# Logitech_Gamepad.net
KiCad netlist of a schematic drawn in EAGLE
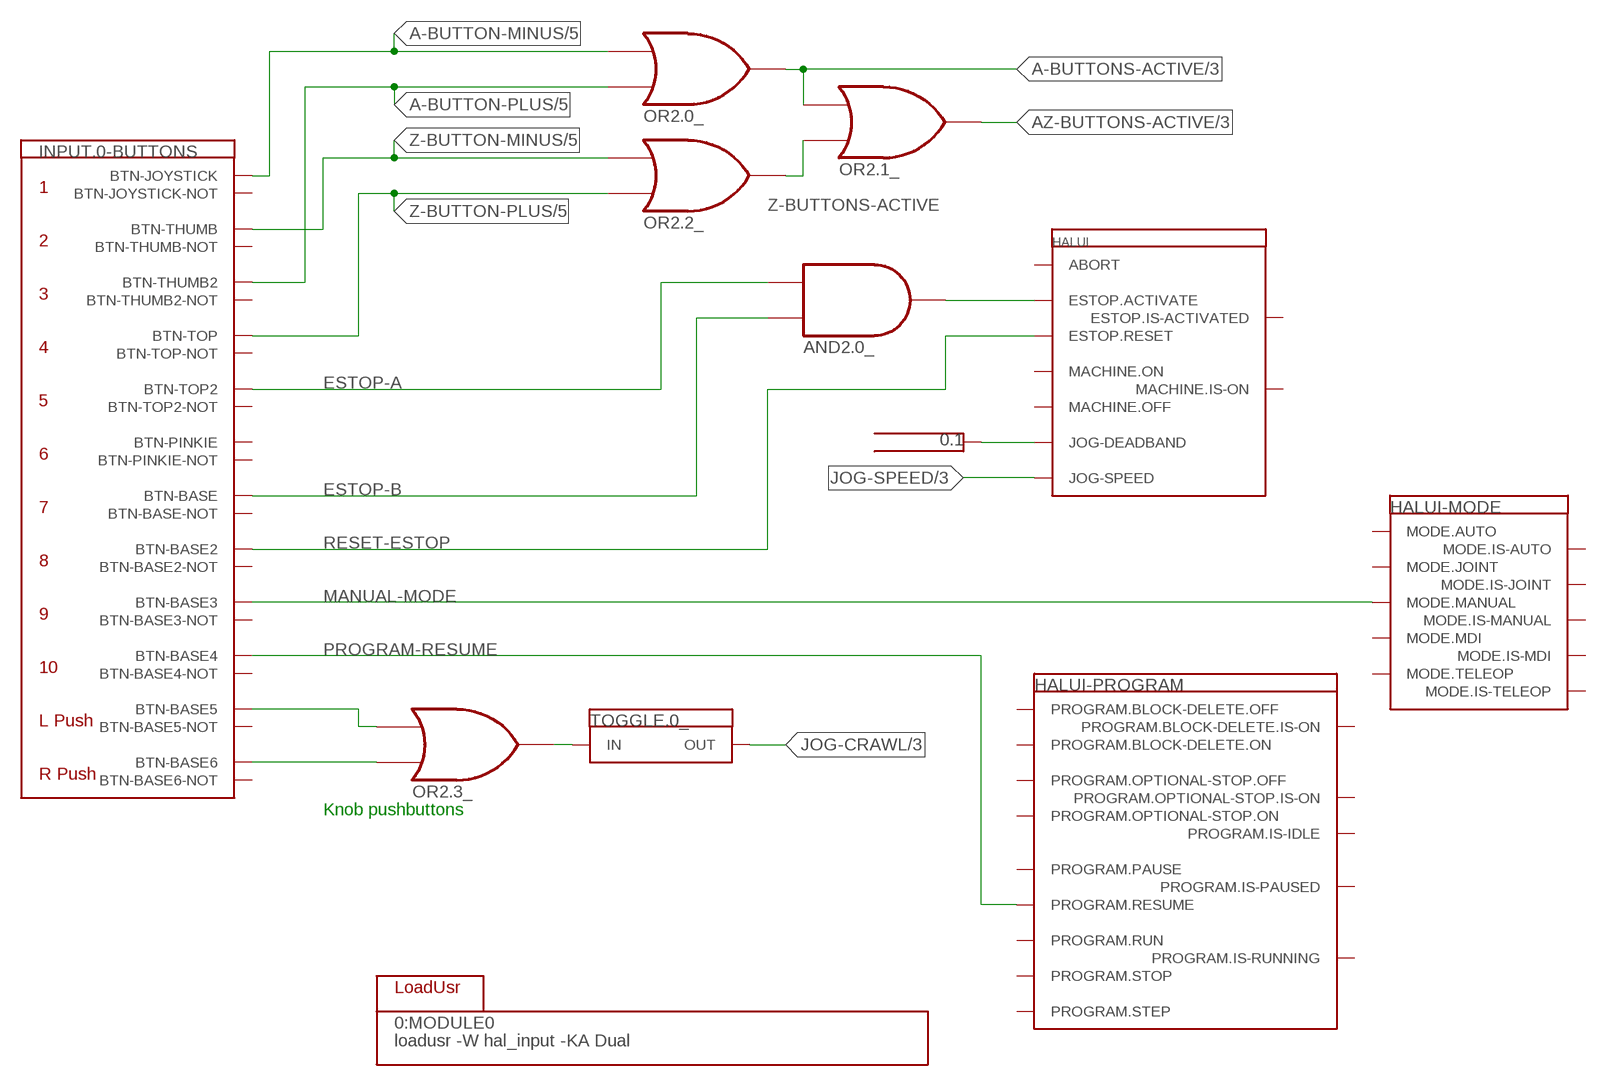
[diagram p0: schematic, sheet 1]
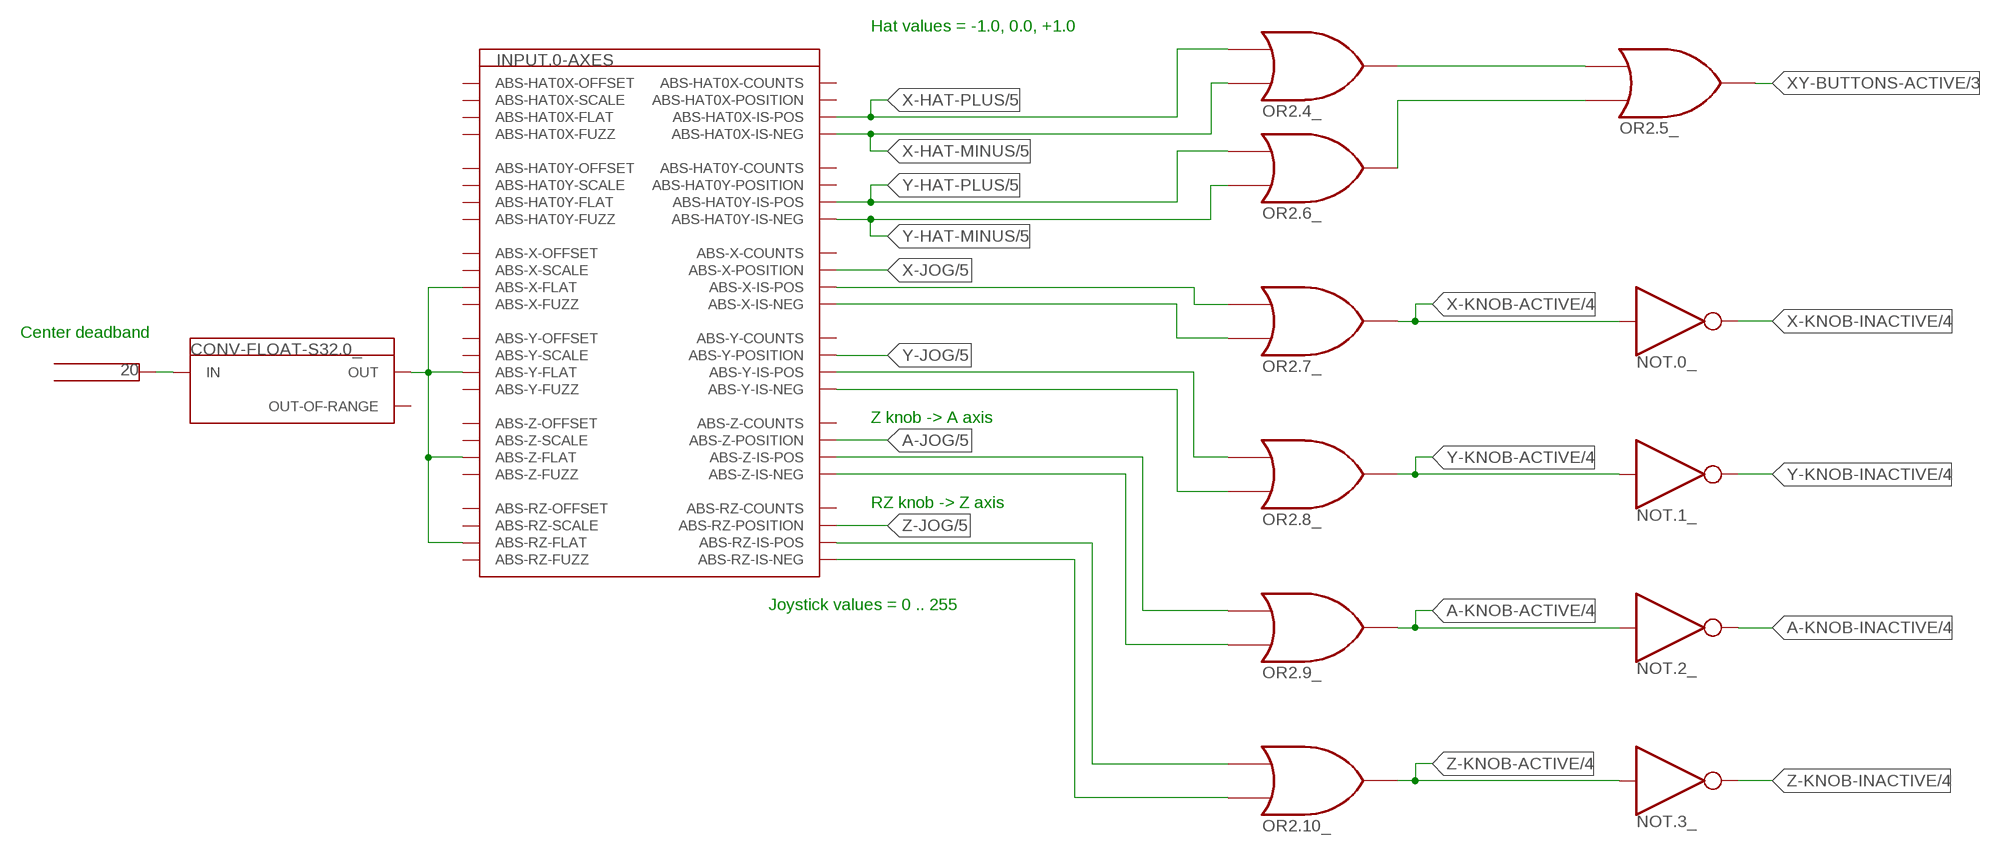
[diagram p1: schematic, sheet 2]
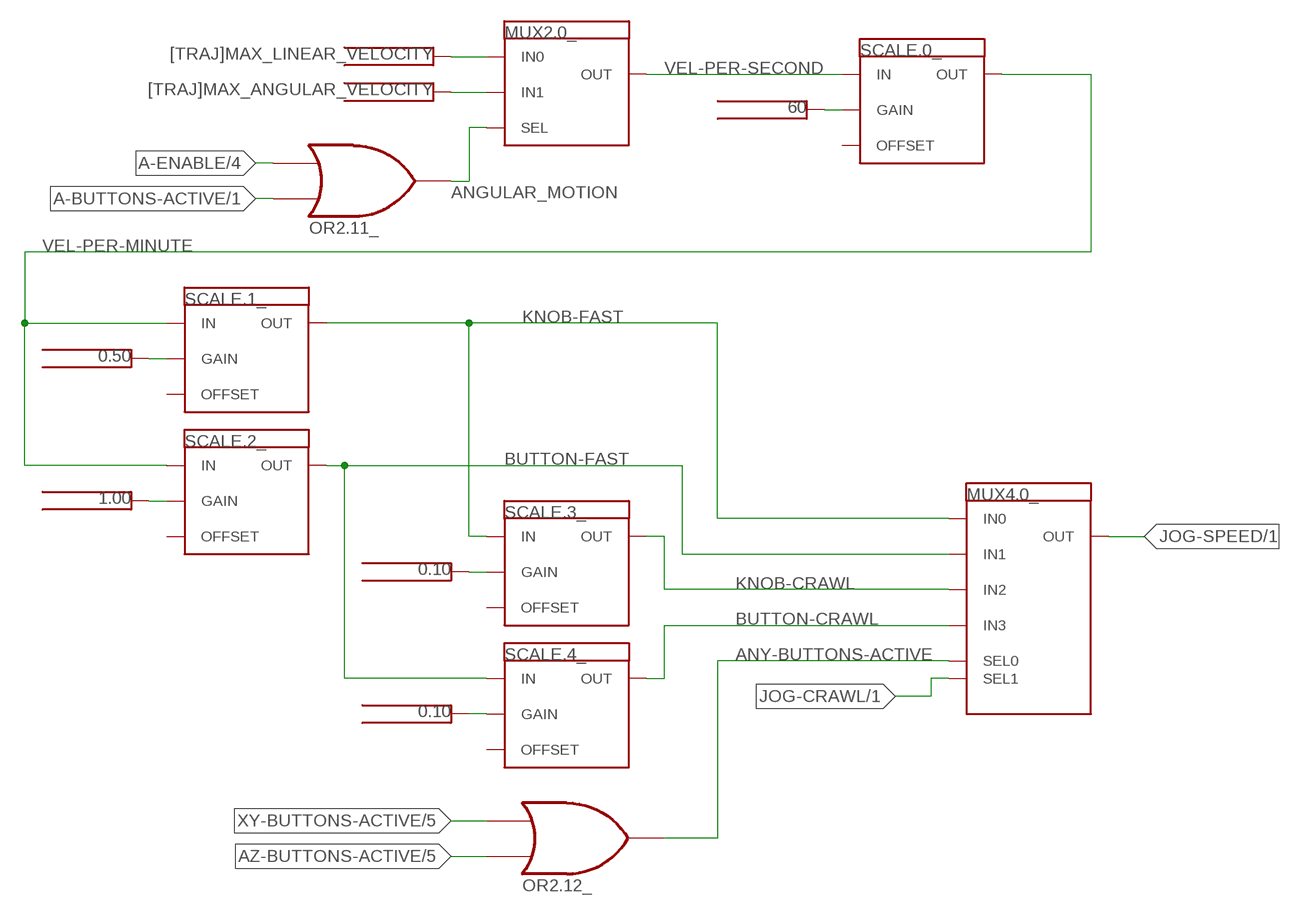
[diagram p2: schematic, sheet 3]
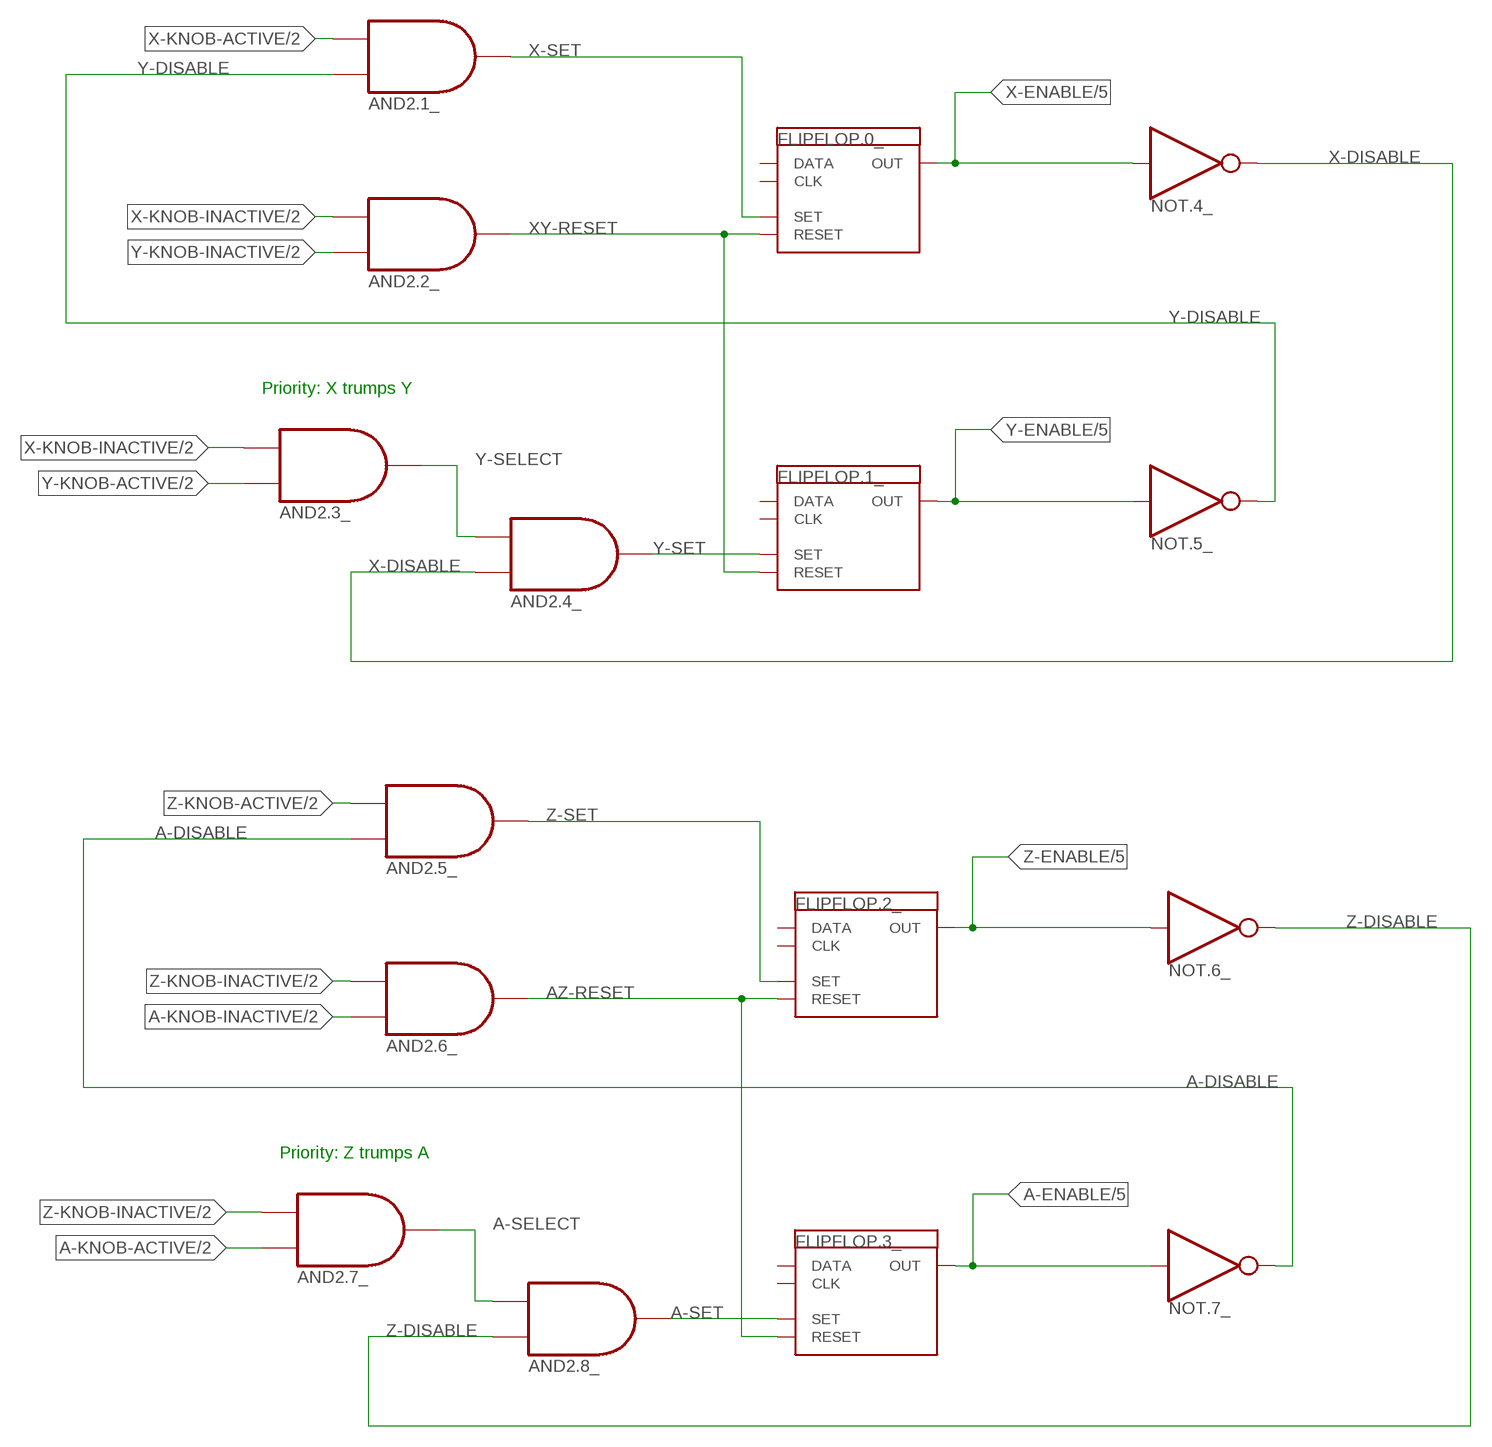
[diagram p3: schematic, sheet 4]
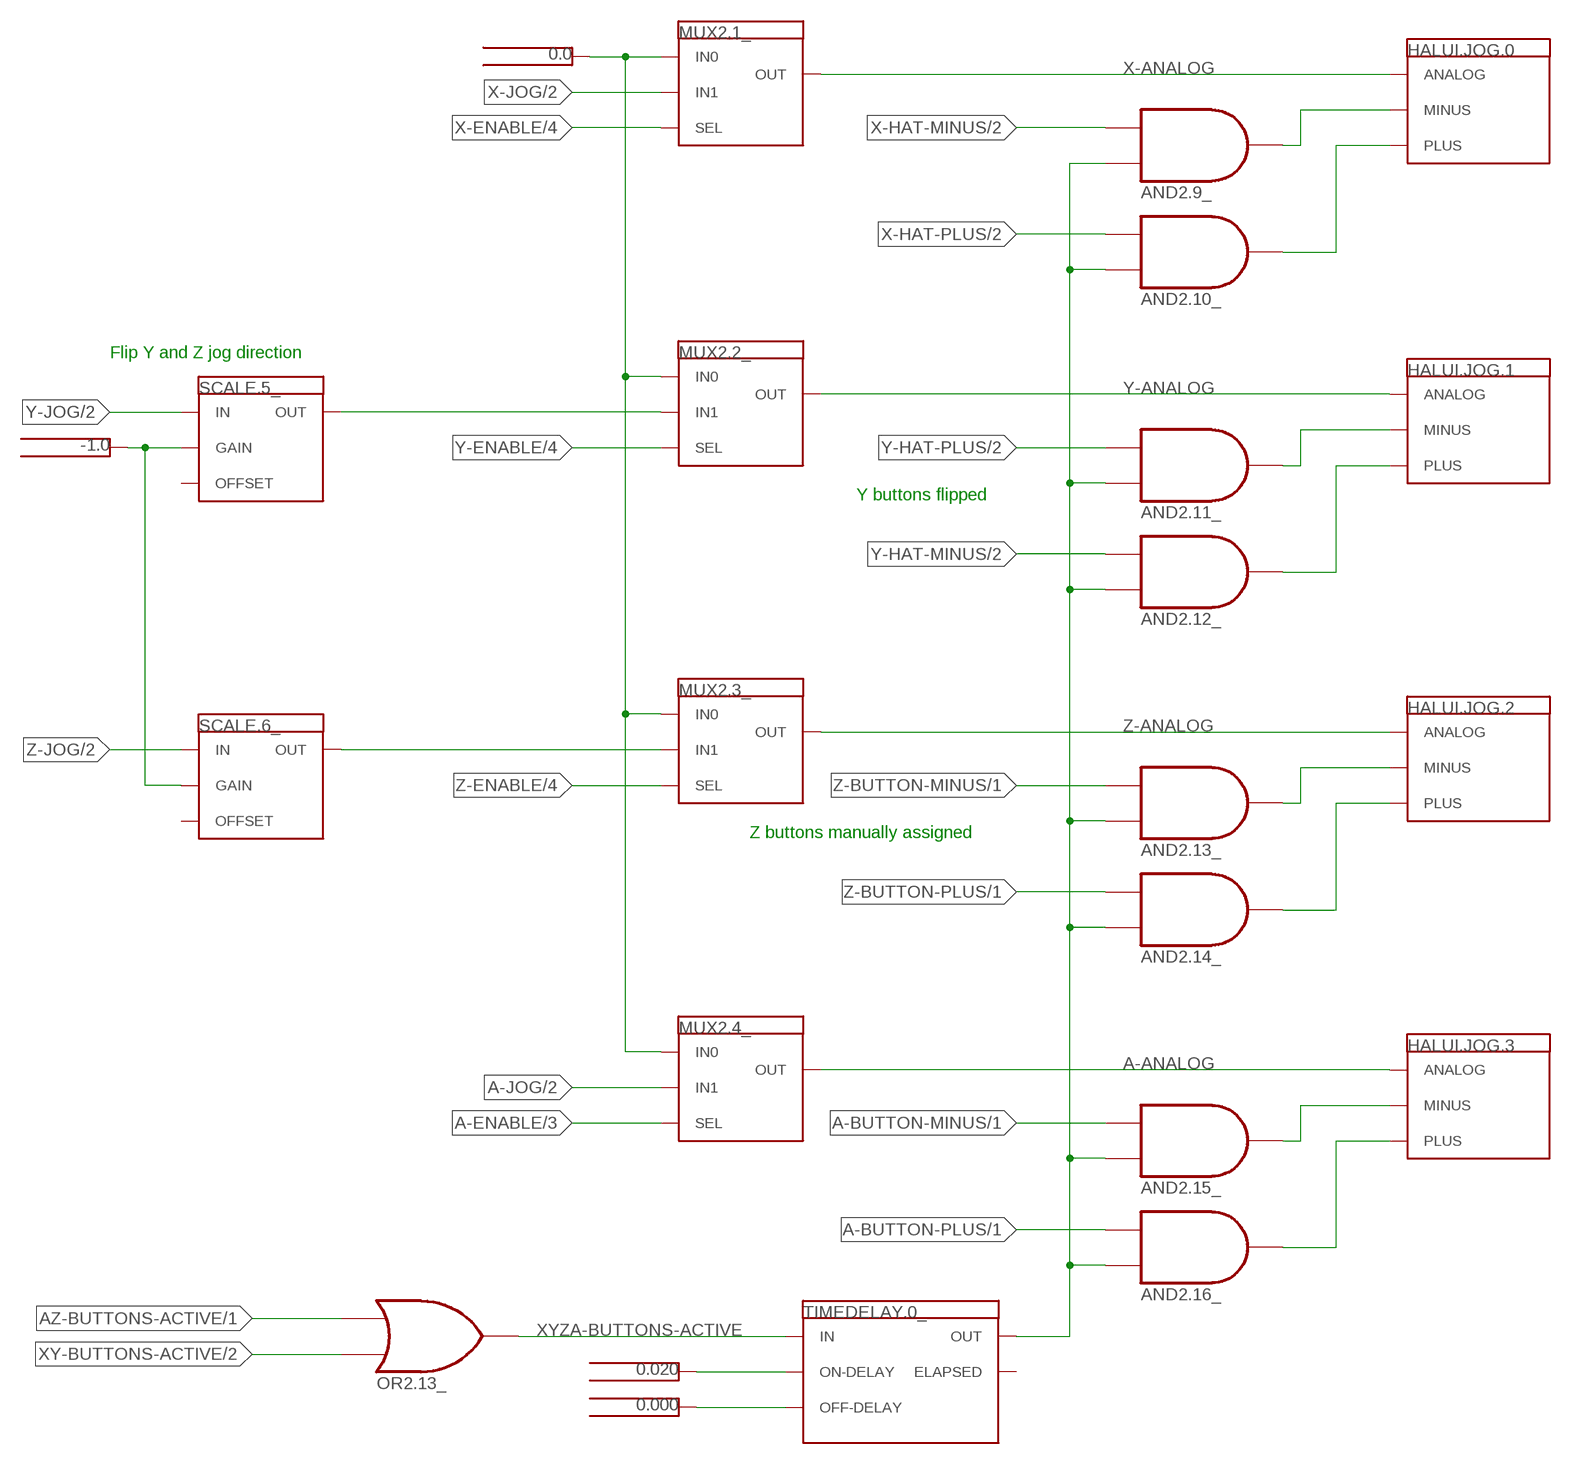
[diagram p4: schematic, sheet 5]
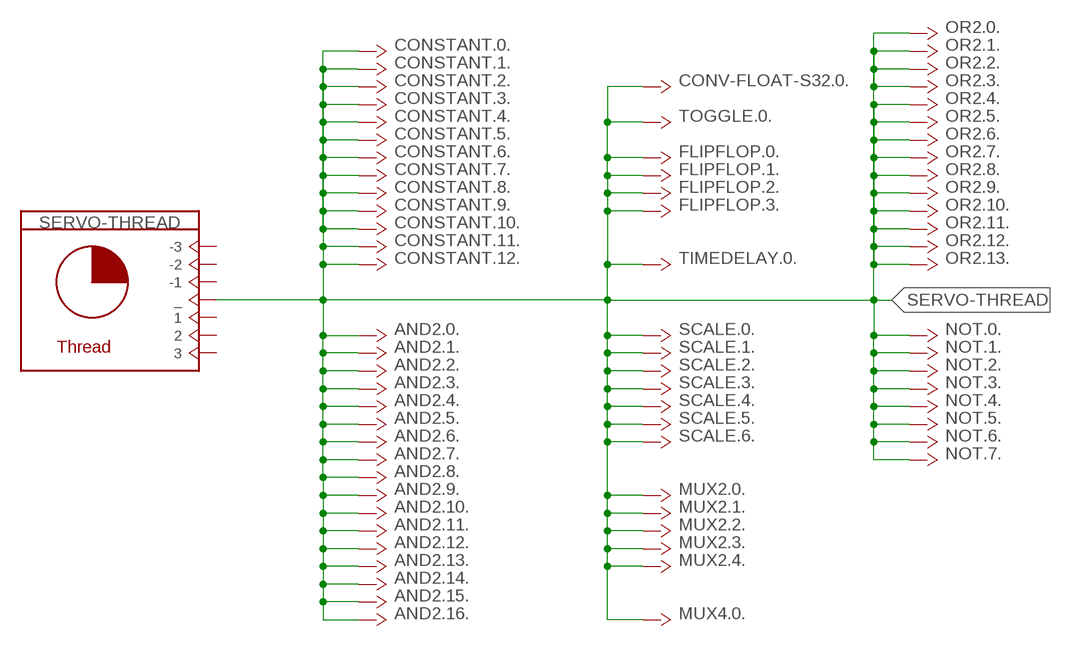
[diagram p5: schematic, sheet 6]

(export (version "E")
  (design (tool "Eeschema 10.0.6"))
  (components
    (comp (ref "AND2.9")
      (value "AND2")
      (footprint "eagle-import:DUMMY")
      (libsource (lib "eagle-import") (part "AND2"))
    )
    (comp (ref "AND2.10")
      (value "AND2")
      (footprint "eagle-import:DUMMY")
      (libsource (lib "eagle-import") (part "AND2"))
    )
    (comp (ref "AND2.11")
      (value "AND2")
      (footprint "eagle-import:DUMMY")
      (libsource (lib "eagle-import") (part "AND2"))
    )
    (comp (ref "AND2.12")
      (value "AND2")
      (footprint "eagle-import:DUMMY")
      (libsource (lib "eagle-import") (part "AND2"))
    )
    (comp (ref "AND2.13")
      (value "AND2")
      (footprint "eagle-import:DUMMY")
      (libsource (lib "eagle-import") (part "AND2"))
    )
    (comp (ref "AND2.14")
      (value "AND2")
      (footprint "eagle-import:DUMMY")
      (libsource (lib "eagle-import") (part "AND2"))
    )
    (comp (ref "AND2.15")
      (value "AND2")
      (footprint "eagle-import:DUMMY")
      (libsource (lib "eagle-import") (part "AND2"))
    )
    (comp (ref "AND2.16")
      (value "AND2")
      (footprint "eagle-import:DUMMY")
      (libsource (lib "eagle-import") (part "AND2"))
    )
    (comp (ref "CONSTANT.9")
      (value "0.0")
      (footprint "eagle-import:DUMMY")
      (libsource (lib "eagle-import") (part "CONSTANT"))
    )
    (comp (ref "CONSTANT.10")
      (value "-1.0")
      (footprint "eagle-import:DUMMY")
      (libsource (lib "eagle-import") (part "CONSTANT"))
    )
    (comp (ref "CONSTANT.11")
      (value "0.020")
      (footprint "eagle-import:DUMMY")
      (libsource (lib "eagle-import") (part "CONSTANT"))
    )
    (comp (ref "CONSTANT.12")
      (value "0.000")
      (footprint "eagle-import:DUMMY")
      (libsource (lib "eagle-import") (part "CONSTANT"))
    )
    (comp (ref "HALUI.JOG.0")
      (value "HALUI.JOG")
      (footprint "eagle-import:DUMMY")
      (libsource (lib "eagle-import") (part "HALUI.JOG"))
    )
    (comp (ref "HALUI.JOG.1")
      (value "HALUI.JOG")
      (footprint "eagle-import:DUMMY")
      (libsource (lib "eagle-import") (part "HALUI.JOG"))
    )
    (comp (ref "HALUI.JOG.2")
      (value "HALUI.JOG")
      (footprint "eagle-import:DUMMY")
      (libsource (lib "eagle-import") (part "HALUI.JOG"))
    )
    (comp (ref "HALUI.JOG.3")
      (value "HALUI.JOG")
      (footprint "eagle-import:DUMMY")
      (libsource (lib "eagle-import") (part "HALUI.JOG"))
    )
    (comp (ref "MUX2.1")
      (value "MUX2")
      (footprint "eagle-import:DUMMY")
      (libsource (lib "eagle-import") (part "MUX2"))
    )
    (comp (ref "MUX2.2")
      (value "MUX2")
      (footprint "eagle-import:DUMMY")
      (libsource (lib "eagle-import") (part "MUX2"))
    )
    (comp (ref "MUX2.3")
      (value "MUX2")
      (footprint "eagle-import:DUMMY")
      (libsource (lib "eagle-import") (part "MUX2"))
    )
    (comp (ref "MUX2.4")
      (value "MUX2")
      (footprint "eagle-import:DUMMY")
      (libsource (lib "eagle-import") (part "MUX2"))
    )
    (comp (ref "OR2.13")
      (value "OR2")
      (footprint "eagle-import:DUMMY")
      (libsource (lib "eagle-import") (part "OR2"))
    )
    (comp (ref "SCALE.5")
      (value "SCALE")
      (footprint "eagle-import:DUMMY")
      (libsource (lib "eagle-import") (part "SCALE"))
    )
    (comp (ref "SCALE.6")
      (value "SCALE")
      (footprint "eagle-import:DUMMY")
      (libsource (lib "eagle-import") (part "SCALE"))
    )
    (comp (ref "TIMEDELAY.0")
      (value "TIMEDELAY")
      (footprint "eagle-import:DUMMY")
      (libsource (lib "eagle-import") (part "TIMEDELAY"))
    )
    (comp (ref "CONSTANT.1")
      (value "20")
      (footprint "eagle-import:DUMMY")
      (libsource (lib "eagle-import") (part "CONSTANT"))
    )
    (comp (ref "CONV-FLOAT-S32.0")
      (value "CONV_FLOAT_S32")
      (footprint "eagle-import:DUMMY")
      (libsource (lib "eagle-import") (part "CONV_FLOAT_S32"))
    )
    (comp (ref "INPUT.0")
      (value "LOGITECH-DUAL-ACTION-GAMEPAD")
      (footprint "eagle-import:DUMMY")
      (libsource (lib "eagle-import") (part "LOGITECH-DUAL-ACTION-GAMEPAD"))
    )
    (comp (ref "NOT.0")
      (value "NOT")
      (footprint "eagle-import:DUMMY")
      (libsource (lib "eagle-import") (part "NOT"))
    )
    (comp (ref "NOT.1")
      (value "NOT")
      (footprint "eagle-import:DUMMY")
      (libsource (lib "eagle-import") (part "NOT"))
    )
    (comp (ref "NOT.2")
      (value "NOT")
      (footprint "eagle-import:DUMMY")
      (libsource (lib "eagle-import") (part "NOT"))
    )
    (comp (ref "NOT.3")
      (value "NOT")
      (footprint "eagle-import:DUMMY")
      (libsource (lib "eagle-import") (part "NOT"))
    )
    (comp (ref "OR2.4")
      (value "OR2")
      (footprint "eagle-import:DUMMY")
      (libsource (lib "eagle-import") (part "OR2"))
    )
    (comp (ref "OR2.5")
      (value "OR2")
      (footprint "eagle-import:DUMMY")
      (libsource (lib "eagle-import") (part "OR2"))
    )
    (comp (ref "OR2.6")
      (value "OR2")
      (footprint "eagle-import:DUMMY")
      (libsource (lib "eagle-import") (part "OR2"))
    )
    (comp (ref "OR2.7")
      (value "OR2")
      (footprint "eagle-import:DUMMY")
      (libsource (lib "eagle-import") (part "OR2"))
    )
    (comp (ref "OR2.8")
      (value "OR2")
      (footprint "eagle-import:DUMMY")
      (libsource (lib "eagle-import") (part "OR2"))
    )
    (comp (ref "OR2.9")
      (value "OR2")
      (footprint "eagle-import:DUMMY")
      (libsource (lib "eagle-import") (part "OR2"))
    )
    (comp (ref "OR2.10")
      (value "OR2")
      (footprint "eagle-import:DUMMY")
      (libsource (lib "eagle-import") (part "OR2"))
    )
    (comp (ref "CONSTANT.2")
      (value "[TRAJ]MAX_LINEAR_VELOCITY")
      (footprint "eagle-import:DUMMY")
      (libsource (lib "eagle-import") (part "CONSTANT"))
    )
    (comp (ref "CONSTANT.3")
      (value "[TRAJ]MAX_ANGULAR_VELOCITY")
      (footprint "eagle-import:DUMMY")
      (libsource (lib "eagle-import") (part "CONSTANT"))
    )
    (comp (ref "CONSTANT.4")
      (value "60")
      (footprint "eagle-import:DUMMY")
      (libsource (lib "eagle-import") (part "CONSTANT"))
    )
    (comp (ref "CONSTANT.5")
      (value "0.50")
      (footprint "eagle-import:DUMMY")
      (libsource (lib "eagle-import") (part "CONSTANT"))
    )
    (comp (ref "CONSTANT.6")
      (value "1.00")
      (footprint "eagle-import:DUMMY")
      (libsource (lib "eagle-import") (part "CONSTANT"))
    )
    (comp (ref "CONSTANT.7")
      (value "0.10")
      (footprint "eagle-import:DUMMY")
      (libsource (lib "eagle-import") (part "CONSTANT"))
    )
    (comp (ref "CONSTANT.8")
      (value "0.10")
      (footprint "eagle-import:DUMMY")
      (libsource (lib "eagle-import") (part "CONSTANT"))
    )
    (comp (ref "MUX2.0")
      (value "MUX2")
      (footprint "eagle-import:DUMMY")
      (libsource (lib "eagle-import") (part "MUX2"))
    )
    (comp (ref "MUX4.0")
      (value "MUX4")
      (footprint "eagle-import:DUMMY")
      (libsource (lib "eagle-import") (part "MUX4"))
    )
    (comp (ref "OR2.11")
      (value "OR2")
      (footprint "eagle-import:DUMMY")
      (libsource (lib "eagle-import") (part "OR2"))
    )
    (comp (ref "OR2.12")
      (value "OR2")
      (footprint "eagle-import:DUMMY")
      (libsource (lib "eagle-import") (part "OR2"))
    )
    (comp (ref "SCALE.0")
      (value "SCALE")
      (footprint "eagle-import:DUMMY")
      (libsource (lib "eagle-import") (part "SCALE"))
    )
    (comp (ref "SCALE.1")
      (value "SCALE")
      (footprint "eagle-import:DUMMY")
      (libsource (lib "eagle-import") (part "SCALE"))
    )
    (comp (ref "SCALE.2")
      (value "SCALE")
      (footprint "eagle-import:DUMMY")
      (libsource (lib "eagle-import") (part "SCALE"))
    )
    (comp (ref "SCALE.3")
      (value "SCALE")
      (footprint "eagle-import:DUMMY")
      (libsource (lib "eagle-import") (part "SCALE"))
    )
    (comp (ref "SCALE.4")
      (value "SCALE")
      (footprint "eagle-import:DUMMY")
      (libsource (lib "eagle-import") (part "SCALE"))
    )
    (comp (ref "AND2.1")
      (value "AND2")
      (footprint "eagle-import:DUMMY")
      (libsource (lib "eagle-import") (part "AND2"))
    )
    (comp (ref "AND2.2")
      (value "AND2")
      (footprint "eagle-import:DUMMY")
      (libsource (lib "eagle-import") (part "AND2"))
    )
    (comp (ref "AND2.3")
      (value "AND2")
      (footprint "eagle-import:DUMMY")
      (libsource (lib "eagle-import") (part "AND2"))
    )
    (comp (ref "AND2.4")
      (value "AND2")
      (footprint "eagle-import:DUMMY")
      (libsource (lib "eagle-import") (part "AND2"))
    )
    (comp (ref "AND2.5")
      (value "AND2")
      (footprint "eagle-import:DUMMY")
      (libsource (lib "eagle-import") (part "AND2"))
    )
    (comp (ref "AND2.6")
      (value "AND2")
      (footprint "eagle-import:DUMMY")
      (libsource (lib "eagle-import") (part "AND2"))
    )
    (comp (ref "AND2.7")
      (value "AND2")
      (footprint "eagle-import:DUMMY")
      (libsource (lib "eagle-import") (part "AND2"))
    )
    (comp (ref "AND2.8")
      (value "AND2")
      (footprint "eagle-import:DUMMY")
      (libsource (lib "eagle-import") (part "AND2"))
    )
    (comp (ref "FLIPFLOP.0")
      (value "FLIPFLOP")
      (footprint "eagle-import:DUMMY")
      (libsource (lib "eagle-import") (part "FLIPFLOP"))
    )
    (comp (ref "FLIPFLOP.1")
      (value "FLIPFLOP")
      (footprint "eagle-import:DUMMY")
      (libsource (lib "eagle-import") (part "FLIPFLOP"))
    )
    (comp (ref "FLIPFLOP.2")
      (value "FLIPFLOP")
      (footprint "eagle-import:DUMMY")
      (libsource (lib "eagle-import") (part "FLIPFLOP"))
    )
    (comp (ref "FLIPFLOP.3")
      (value "FLIPFLOP")
      (footprint "eagle-import:DUMMY")
      (libsource (lib "eagle-import") (part "FLIPFLOP"))
    )
    (comp (ref "NOT.4")
      (value "NOT")
      (footprint "eagle-import:DUMMY")
      (libsource (lib "eagle-import") (part "NOT"))
    )
    (comp (ref "NOT.5")
      (value "NOT")
      (footprint "eagle-import:DUMMY")
      (libsource (lib "eagle-import") (part "NOT"))
    )
    (comp (ref "NOT.6")
      (value "NOT")
      (footprint "eagle-import:DUMMY")
      (libsource (lib "eagle-import") (part "NOT"))
    )
    (comp (ref "NOT.7")
      (value "NOT")
      (footprint "eagle-import:DUMMY")
      (libsource (lib "eagle-import") (part "NOT"))
    )
    (comp (ref "AND2.0")
      (value "AND2")
      (footprint "eagle-import:DUMMY")
      (libsource (lib "eagle-import") (part "AND2"))
    )
    (comp (ref "CONSTANT.0")
      (value "0.1")
      (footprint "eagle-import:DUMMY")
      (libsource (lib "eagle-import") (part "CONSTANT"))
    )
    (comp (ref "OR2.0")
      (value "OR2")
      (footprint "eagle-import:DUMMY")
      (libsource (lib "eagle-import") (part "OR2"))
    )
    (comp (ref "OR2.1")
      (value "OR2")
      (footprint "eagle-import:DUMMY")
      (libsource (lib "eagle-import") (part "OR2"))
    )
    (comp (ref "OR2.2")
      (value "OR2")
      (footprint "eagle-import:DUMMY")
      (libsource (lib "eagle-import") (part "OR2"))
    )
    (comp (ref "OR2.3")
      (value "OR2")
      (footprint "eagle-import:DUMMY")
      (libsource (lib "eagle-import") (part "OR2"))
    )
    (comp (ref "SERVO-THREAD")
      (value "THREAD")
      (footprint "eagle-import:DUMMY")
      (libsource (lib "eagle-import") (part "THREAD"))
    )
    (comp (ref "TOGGLE.0")
      (value "TOGGLE")
      (footprint "eagle-import:DUMMY")
      (libsource (lib "eagle-import") (part "TOGGLE"))
    )
    (comp (ref "HALUI")
      (value "HALUI")
      (footprint "eagle-import:DUMMY")
      (libsource (lib "eagle-import") (part "HALUI"))
    )
  )
  (nets
    (net (code "1") (name "A-ANALOG") (class "Default")
      (node (ref "HALUI.JOG.3") (pin "P$1") (pinfunction "ANALOG_P$1") (pintype "input"))
      (node (ref "MUX2.4") (pin "P$4") (pinfunction "OUT_P$4") (pintype "output"))
    )
    (net (code "2") (name "A-BUTTON-MINUS") (class "Default")
      (node (ref "AND2.15") (pin "P$1") (pinfunction "IN0_P$1") (pintype "input"))
      (node (ref "INPUT.0") (pin "P$61") (pinfunction "BTN-JOYSTICK_P$61") (pintype "output"))
      (node (ref "OR2.0") (pin "P$2") (pinfunction "IN0_P$2") (pintype "input"))
    )
    (net (code "3") (name "A-BUTTON-PLUS") (class "Default")
      (node (ref "AND2.16") (pin "P$1") (pinfunction "IN0_P$1") (pintype "input"))
      (node (ref "INPUT.0") (pin "P$67") (pinfunction "BTN-THUMB2_P$67") (pintype "output"))
      (node (ref "OR2.0") (pin "P$3") (pinfunction "IN1_P$3") (pintype "input"))
    )
    (net (code "4") (name "A-BUTTONS-ACTIVE") (class "Default")
      (node (ref "OR2.0") (pin "P$4") (pinfunction "OUT_P$4") (pintype "output"))
      (node (ref "OR2.1") (pin "P$2") (pinfunction "IN0_P$2") (pintype "input"))
      (node (ref "OR2.11") (pin "P$3") (pinfunction "IN1_P$3") (pintype "input"))
    )
    (net (code "5") (name "A-DISABLE") (class "Default")
      (node (ref "AND2.5") (pin "P$2") (pinfunction "IN1_P$2") (pintype "input"))
      (node (ref "NOT.7") (pin "P$2") (pinfunction "OUT_P$2") (pintype "output"))
    )
    (net (code "6") (name "A-ENABLE") (class "Default")
      (node (ref "FLIPFLOP.3") (pin "P$3") (pinfunction "OUT_P$3") (pintype "output"))
      (node (ref "MUX2.4") (pin "P$5") (pinfunction "SEL_P$5") (pintype "input"))
      (node (ref "NOT.7") (pin "P$1") (pinfunction "IN_P$1") (pintype "input"))
      (node (ref "OR2.11") (pin "P$2") (pinfunction "IN0_P$2") (pintype "input"))
    )
    (net (code "7") (name "A-JOG") (class "Default")
      (node (ref "INPUT.0") (pin "P$47") (pinfunction "ABS-Z-POSITION_P$47") (pintype "output"))
      (node (ref "MUX2.4") (pin "P$3") (pinfunction "IN1_P$3") (pintype "input"))
    )
    (net (code "8") (name "A-KNOB-ACTIVE") (class "Default")
      (node (ref "AND2.7") (pin "P$2") (pinfunction "IN1_P$2") (pintype "input"))
      (node (ref "NOT.2") (pin "P$1") (pinfunction "IN_P$1") (pintype "input"))
      (node (ref "OR2.9") (pin "P$4") (pinfunction "OUT_P$4") (pintype "output"))
    )
    (net (code "9") (name "A-KNOB-INACTIVE") (class "Default")
      (node (ref "AND2.6") (pin "P$2") (pinfunction "IN1_P$2") (pintype "input"))
      (node (ref "NOT.2") (pin "P$2") (pinfunction "OUT_P$2") (pintype "output"))
    )
    (net (code "10") (name "A-SELECT") (class "Default")
      (node (ref "AND2.7") (pin "P$3") (pinfunction "OUT_P$3") (pintype "output"))
      (node (ref "AND2.8") (pin "P$1") (pinfunction "IN0_P$1") (pintype "input"))
    )
    (net (code "11") (name "A-SET") (class "Default")
      (node (ref "AND2.8") (pin "P$3") (pinfunction "OUT_P$3") (pintype "output"))
      (node (ref "FLIPFLOP.3") (pin "P$5") (pinfunction "SET_P$5") (pintype "input"))
    )
    (net (code "12") (name "ANGULAR_MOTION") (class "Default")
      (node (ref "MUX2.0") (pin "P$5") (pinfunction "SEL_P$5") (pintype "input"))
      (node (ref "OR2.11") (pin "P$4") (pinfunction "OUT_P$4") (pintype "output"))
    )
    (net (code "13") (name "ANY-BUTTONS-ACTIVE") (class "Default")
      (node (ref "MUX4.0") (pin "P$7") (pinfunction "SEL0_P$7") (pintype "input"))
      (node (ref "OR2.12") (pin "P$4") (pinfunction "OUT_P$4") (pintype "output"))
    )
    (net (code "14") (name "AZ-BUTTONS-ACTIVE") (class "Default")
      (node (ref "OR2.1") (pin "P$4") (pinfunction "OUT_P$4") (pintype "output"))
      (node (ref "OR2.12") (pin "P$3") (pinfunction "IN1_P$3") (pintype "input"))
      (node (ref "OR2.13") (pin "P$2") (pinfunction "IN0_P$2") (pintype "input"))
    )
    (net (code "15") (name "AZ-RESET") (class "Default")
      (node (ref "AND2.6") (pin "P$3") (pinfunction "OUT_P$3") (pintype "output"))
      (node (ref "FLIPFLOP.2") (pin "P$4") (pinfunction "RESET_P$4") (pintype "input"))
      (node (ref "FLIPFLOP.3") (pin "P$4") (pinfunction "RESET_P$4") (pintype "input"))
    )
    (net (code "16") (name "BUTTON-CRAWL") (class "Default")
      (node (ref "MUX4.0") (pin "P$5") (pinfunction "IN3_P$5") (pintype "input"))
      (node (ref "SCALE.4") (pin "P$5") (pinfunction "OUT_P$5") (pintype "output"))
    )
    (net (code "17") (name "BUTTON-FAST") (class "Default")
      (node (ref "MUX4.0") (pin "P$3") (pinfunction "IN1_P$3") (pintype "input"))
      (node (ref "SCALE.2") (pin "P$5") (pinfunction "OUT_P$5") (pintype "output"))
      (node (ref "SCALE.4") (pin "P$3") (pinfunction "IN_P$3") (pintype "input"))
    )
    (net (code "18") (name "ESTOP-A") (class "Default")
      (node (ref "AND2.0") (pin "P$1") (pinfunction "IN0_P$1") (pintype "input"))
      (node (ref "INPUT.0") (pin "P$71") (pinfunction "BTN-TOP2_P$71") (pintype "output"))
    )
    (net (code "19") (name "ESTOP-B") (class "Default")
      (node (ref "AND2.0") (pin "P$2") (pinfunction "IN1_P$2") (pintype "input"))
      (node (ref "INPUT.0") (pin "P$49") (pinfunction "BTN-BASE_P$49") (pintype "output"))
    )
    (net (code "20") (name "JOG-CRAWL") (class "Default")
      (node (ref "MUX4.0") (pin "P$8") (pinfunction "SEL1_P$8") (pintype "input"))
      (node (ref "TOGGLE.0") (pin "P$3") (pinfunction "OUT_P$3") (pintype "output"))
    )
    (net (code "21") (name "JOG-SPEED") (class "Default")
      (node (ref "HALUI") (pin "P$82") (pinfunction "JOG-SPEED_P$82") (pintype "input"))
      (node (ref "MUX4.0") (pin "P$6") (pinfunction "OUT_P$6") (pintype "output"))
    )
    (net (code "22") (name "KNOB-CRAWL") (class "Default")
      (node (ref "MUX4.0") (pin "P$4") (pinfunction "IN2_P$4") (pintype "input"))
      (node (ref "SCALE.3") (pin "P$5") (pinfunction "OUT_P$5") (pintype "output"))
    )
    (net (code "23") (name "KNOB-FAST") (class "Default")
      (node (ref "MUX4.0") (pin "P$2") (pinfunction "IN0_P$2") (pintype "input"))
      (node (ref "SCALE.1") (pin "P$5") (pinfunction "OUT_P$5") (pintype "output"))
      (node (ref "SCALE.3") (pin "P$3") (pinfunction "IN_P$3") (pintype "input"))
    )
    (net (code "24") (name "MANUAL-MODE") (class "Default")
      (node (ref "HALUI") (pin "P$72") (pinfunction "MODE.MANUAL_P$72") (pintype "input"))
      (node (ref "INPUT.0") (pin "P$53") (pinfunction "BTN-BASE3_P$53") (pintype "output"))
    )
    (net (code "25") (name "Net-(AND2.0B-OUT)") (class "Default")
      (node (ref "AND2.0") (pin "P$3") (pinfunction "OUT_P$3") (pintype "output"))
      (node (ref "HALUI") (pin "P$2") (pinfunction "ESTOP.ACTIVATE_P$2") (pintype "input"))
    )
    (net (code "26") (name "Net-(AND2.9B-OUT)") (class "Default")
      (node (ref "AND2.9") (pin "P$3") (pinfunction "OUT_P$3") (pintype "output"))
      (node (ref "HALUI.JOG.0") (pin "P$2") (pinfunction "MINUS_P$2") (pintype "input"))
    )
    (net (code "27") (name "Net-(AND2.10B-IN1)") (class "Default")
      (node (ref "AND2.10") (pin "P$2") (pinfunction "IN1_P$2") (pintype "input"))
      (node (ref "AND2.11") (pin "P$2") (pinfunction "IN1_P$2") (pintype "input"))
      (node (ref "AND2.12") (pin "P$2") (pinfunction "IN1_P$2") (pintype "input"))
      (node (ref "AND2.13") (pin "P$2") (pinfunction "IN1_P$2") (pintype "input"))
      (node (ref "AND2.14") (pin "P$2") (pinfunction "IN1_P$2") (pintype "input"))
      (node (ref "AND2.15") (pin "P$2") (pinfunction "IN1_P$2") (pintype "input"))
      (node (ref "AND2.16") (pin "P$2") (pinfunction "IN1_P$2") (pintype "input"))
      (node (ref "AND2.9") (pin "P$2") (pinfunction "IN1_P$2") (pintype "input"))
      (node (ref "TIMEDELAY.0") (pin "P$5") (pinfunction "OUT_P$5") (pintype "output"))
    )
    (net (code "28") (name "Net-(AND2.10B-OUT)") (class "Default")
      (node (ref "AND2.10") (pin "P$3") (pinfunction "OUT_P$3") (pintype "output"))
      (node (ref "HALUI.JOG.0") (pin "P$3") (pinfunction "PLUS_P$3") (pintype "input"))
    )
    (net (code "29") (name "Net-(AND2.11B-OUT)") (class "Default")
      (node (ref "AND2.11") (pin "P$3") (pinfunction "OUT_P$3") (pintype "output"))
      (node (ref "HALUI.JOG.1") (pin "P$2") (pinfunction "MINUS_P$2") (pintype "input"))
    )
    (net (code "30") (name "Net-(AND2.12B-OUT)") (class "Default")
      (node (ref "AND2.12") (pin "P$3") (pinfunction "OUT_P$3") (pintype "output"))
      (node (ref "HALUI.JOG.1") (pin "P$3") (pinfunction "PLUS_P$3") (pintype "input"))
    )
    (net (code "31") (name "Net-(AND2.13B-OUT)") (class "Default")
      (node (ref "AND2.13") (pin "P$3") (pinfunction "OUT_P$3") (pintype "output"))
      (node (ref "HALUI.JOG.2") (pin "P$2") (pinfunction "MINUS_P$2") (pintype "input"))
    )
    (net (code "32") (name "Net-(AND2.14B-OUT)") (class "Default")
      (node (ref "AND2.14") (pin "P$3") (pinfunction "OUT_P$3") (pintype "output"))
      (node (ref "HALUI.JOG.2") (pin "P$3") (pinfunction "PLUS_P$3") (pintype "input"))
    )
    (net (code "33") (name "Net-(AND2.15B-OUT)") (class "Default")
      (node (ref "AND2.15") (pin "P$3") (pinfunction "OUT_P$3") (pintype "output"))
      (node (ref "HALUI.JOG.3") (pin "P$2") (pinfunction "MINUS_P$2") (pintype "input"))
    )
    (net (code "34") (name "Net-(AND2.16B-OUT)") (class "Default")
      (node (ref "AND2.16") (pin "P$3") (pinfunction "OUT_P$3") (pintype "output"))
      (node (ref "HALUI.JOG.3") (pin "P$3") (pinfunction "PLUS_P$3") (pintype "input"))
    )
    (net (code "35") (name "Net-(CONSTANT.0B-OUT)") (class "Default")
      (node (ref "CONSTANT.0") (pin "P$2") (pinfunction "OUT_P$2") (pintype "output"))
      (node (ref "HALUI") (pin "P$81") (pinfunction "JOG-DEADBAND_P$81") (pintype "input"))
    )
    (net (code "36") (name "Net-(CONSTANT.1B-OUT)") (class "Default")
      (node (ref "CONSTANT.1") (pin "P$2") (pinfunction "OUT_P$2") (pintype "output"))
      (node (ref "CONV-FLOAT-S32.0") (pin "P$3") (pinfunction "IN_P$3") (pintype "input"))
    )
    (net (code "37") (name "Net-(CONSTANT.2B-OUT)") (class "Default")
      (node (ref "CONSTANT.2") (pin "P$2") (pinfunction "OUT_P$2") (pintype "output"))
      (node (ref "MUX2.0") (pin "P$2") (pinfunction "IN0_P$2") (pintype "input"))
    )
    (net (code "38") (name "Net-(CONSTANT.3B-OUT)") (class "Default")
      (node (ref "CONSTANT.3") (pin "P$2") (pinfunction "OUT_P$2") (pintype "output"))
      (node (ref "MUX2.0") (pin "P$3") (pinfunction "IN1_P$3") (pintype "input"))
    )
    (net (code "39") (name "Net-(CONSTANT.4B-OUT)") (class "Default")
      (node (ref "CONSTANT.4") (pin "P$2") (pinfunction "OUT_P$2") (pintype "output"))
      (node (ref "SCALE.0") (pin "P$2") (pinfunction "GAIN_P$2") (pintype "input"))
    )
    (net (code "40") (name "Net-(CONSTANT.5B-OUT)") (class "Default")
      (node (ref "CONSTANT.5") (pin "P$2") (pinfunction "OUT_P$2") (pintype "output"))
      (node (ref "SCALE.1") (pin "P$2") (pinfunction "GAIN_P$2") (pintype "input"))
    )
    (net (code "41") (name "Net-(CONSTANT.6B-OUT)") (class "Default")
      (node (ref "CONSTANT.6") (pin "P$2") (pinfunction "OUT_P$2") (pintype "output"))
      (node (ref "SCALE.2") (pin "P$2") (pinfunction "GAIN_P$2") (pintype "input"))
    )
    (net (code "42") (name "Net-(CONSTANT.7B-OUT)") (class "Default")
      (node (ref "CONSTANT.7") (pin "P$2") (pinfunction "OUT_P$2") (pintype "output"))
      (node (ref "SCALE.3") (pin "P$2") (pinfunction "GAIN_P$2") (pintype "input"))
    )
    (net (code "43") (name "Net-(CONSTANT.8B-OUT)") (class "Default")
      (node (ref "CONSTANT.8") (pin "P$2") (pinfunction "OUT_P$2") (pintype "output"))
      (node (ref "SCALE.4") (pin "P$2") (pinfunction "GAIN_P$2") (pintype "input"))
    )
    (net (code "44") (name "Net-(CONSTANT.9B-OUT)") (class "Default")
      (node (ref "CONSTANT.9") (pin "P$2") (pinfunction "OUT_P$2") (pintype "output"))
      (node (ref "MUX2.1") (pin "P$2") (pinfunction "IN0_P$2") (pintype "input"))
      (node (ref "MUX2.2") (pin "P$2") (pinfunction "IN0_P$2") (pintype "input"))
      (node (ref "MUX2.3") (pin "P$2") (pinfunction "IN0_P$2") (pintype "input"))
      (node (ref "MUX2.4") (pin "P$2") (pinfunction "IN0_P$2") (pintype "input"))
    )
    (net (code "45") (name "Net-(CONSTANT.10B-OUT)") (class "Default")
      (node (ref "CONSTANT.10") (pin "P$2") (pinfunction "OUT_P$2") (pintype "output"))
      (node (ref "SCALE.5") (pin "P$2") (pinfunction "GAIN_P$2") (pintype "input"))
      (node (ref "SCALE.6") (pin "P$2") (pinfunction "GAIN_P$2") (pintype "input"))
    )
    (net (code "46") (name "Net-(CONSTANT.11B-OUT)") (class "Default")
      (node (ref "CONSTANT.11") (pin "P$2") (pinfunction "OUT_P$2") (pintype "output"))
      (node (ref "TIMEDELAY.0") (pin "P$4") (pinfunction "ON-DELAY_P$4") (pintype "input"))
    )
    (net (code "47") (name "Net-(CONSTANT.12B-OUT)") (class "Default")
      (node (ref "CONSTANT.12") (pin "P$2") (pinfunction "OUT_P$2") (pintype "output"))
      (node (ref "TIMEDELAY.0") (pin "P$3") (pinfunction "OFF-DELAY_P$3") (pintype "input"))
    )
    (net (code "48") (name "Net-(CONV-FLOAT-S32.0C-OUT)") (class "Default")
      (node (ref "CONV-FLOAT-S32.0") (pin "P$4") (pinfunction "OUT_P$4") (pintype "output"))
      (node (ref "INPUT.0") (pin "P$18") (pinfunction "ABS-RZ-FLAT_P$18") (pintype "input"))
      (node (ref "INPUT.0") (pin "P$26") (pinfunction "ABS-X-FLAT_P$26") (pintype "input"))
      (node (ref "INPUT.0") (pin "P$34") (pinfunction "ABS-Y-FLAT_P$34") (pintype "input"))
      (node (ref "INPUT.0") (pin "P$42") (pinfunction "ABS-Z-FLAT_P$42") (pintype "input"))
    )
    (net (code "49") (name "Net-(INPUT.0A-ABS-RZ-IS-NEG)") (class "Default")
      (node (ref "INPUT.0") (pin "P$20") (pinfunction "ABS-RZ-IS-NEG_P$20") (pintype "output"))
      (node (ref "OR2.10") (pin "P$3") (pinfunction "IN1_P$3") (pintype "input"))
    )
    (net (code "50") (name "Net-(INPUT.0A-ABS-RZ-IS-POS)") (class "Default")
      (node (ref "INPUT.0") (pin "P$21") (pinfunction "ABS-RZ-IS-POS_P$21") (pintype "output"))
      (node (ref "OR2.10") (pin "P$2") (pinfunction "IN0_P$2") (pintype "input"))
    )
    (net (code "51") (name "Net-(INPUT.0A-ABS-X-IS-NEG)") (class "Default")
      (node (ref "INPUT.0") (pin "P$28") (pinfunction "ABS-X-IS-NEG_P$28") (pintype "output"))
      (node (ref "OR2.7") (pin "P$3") (pinfunction "IN1_P$3") (pintype "input"))
    )
    (net (code "52") (name "Net-(INPUT.0A-ABS-X-IS-POS)") (class "Default")
      (node (ref "INPUT.0") (pin "P$29") (pinfunction "ABS-X-IS-POS_P$29") (pintype "output"))
      (node (ref "OR2.7") (pin "P$2") (pinfunction "IN0_P$2") (pintype "input"))
    )
    (net (code "53") (name "Net-(INPUT.0A-ABS-Y-IS-NEG)") (class "Default")
      (node (ref "INPUT.0") (pin "P$36") (pinfunction "ABS-Y-IS-NEG_P$36") (pintype "output"))
      (node (ref "OR2.8") (pin "P$3") (pinfunction "IN1_P$3") (pintype "input"))
    )
    (net (code "54") (name "Net-(INPUT.0A-ABS-Y-IS-POS)") (class "Default")
      (node (ref "INPUT.0") (pin "P$37") (pinfunction "ABS-Y-IS-POS_P$37") (pintype "output"))
      (node (ref "OR2.8") (pin "P$2") (pinfunction "IN0_P$2") (pintype "input"))
    )
    (net (code "55") (name "Net-(INPUT.0A-ABS-Z-IS-NEG)") (class "Default")
      (node (ref "INPUT.0") (pin "P$44") (pinfunction "ABS-Z-IS-NEG_P$44") (pintype "output"))
      (node (ref "OR2.9") (pin "P$3") (pinfunction "IN1_P$3") (pintype "input"))
    )
    (net (code "56") (name "Net-(INPUT.0A-ABS-Z-IS-POS)") (class "Default")
      (node (ref "INPUT.0") (pin "P$45") (pinfunction "ABS-Z-IS-POS_P$45") (pintype "output"))
      (node (ref "OR2.9") (pin "P$2") (pinfunction "IN0_P$2") (pintype "input"))
    )
    (net (code "57") (name "Net-(INPUT.0B-BTN-BASE5)") (class "Default")
      (node (ref "INPUT.0") (pin "P$57") (pinfunction "BTN-BASE5_P$57") (pintype "output"))
      (node (ref "OR2.3") (pin "P$2") (pinfunction "IN0_P$2") (pintype "input"))
    )
    (net (code "58") (name "Net-(INPUT.0B-BTN-BASE6)") (class "Default")
      (node (ref "INPUT.0") (pin "P$59") (pinfunction "BTN-BASE6_P$59") (pintype "output"))
      (node (ref "OR2.3") (pin "P$3") (pinfunction "IN1_P$3") (pintype "input"))
    )
    (net (code "59") (name "Net-(MUX2.2B-IN1)") (class "Default")
      (node (ref "MUX2.2") (pin "P$3") (pinfunction "IN1_P$3") (pintype "input"))
      (node (ref "SCALE.5") (pin "P$5") (pinfunction "OUT_P$5") (pintype "output"))
    )
    (net (code "60") (name "Net-(MUX2.3B-IN1)") (class "Default")
      (node (ref "MUX2.3") (pin "P$3") (pinfunction "IN1_P$3") (pintype "input"))
      (node (ref "SCALE.6") (pin "P$5") (pinfunction "OUT_P$5") (pintype "output"))
    )
    (net (code "61") (name "Net-(OR2.3B-OUT)") (class "Default")
      (node (ref "OR2.3") (pin "P$4") (pinfunction "OUT_P$4") (pintype "output"))
      (node (ref "TOGGLE.0") (pin "P$2") (pinfunction "IN_P$2") (pintype "input"))
    )
    (net (code "62") (name "Net-(OR2.4B-OUT)") (class "Default")
      (node (ref "OR2.4") (pin "P$4") (pinfunction "OUT_P$4") (pintype "output"))
      (node (ref "OR2.5") (pin "P$2") (pinfunction "IN0_P$2") (pintype "input"))
    )
    (net (code "63") (name "Net-(OR2.5B-IN1)") (class "Default")
      (node (ref "OR2.5") (pin "P$3") (pinfunction "IN1_P$3") (pintype "input"))
      (node (ref "OR2.6") (pin "P$4") (pinfunction "OUT_P$4") (pintype "output"))
    )
    (net (code "64") (name "PROGRAM-RESUME") (class "Default")
      (node (ref "HALUI") (pin "P$43") (pinfunction "PROGRAM.RESUME_P$43") (pintype "input"))
      (node (ref "INPUT.0") (pin "P$55") (pinfunction "BTN-BASE4_P$55") (pintype "output"))
    )
    (net (code "65") (name "RESET-ESTOP") (class "Default")
      (node (ref "HALUI") (pin "P$4") (pinfunction "ESTOP.RESET_P$4") (pintype "input"))
      (node (ref "INPUT.0") (pin "P$51") (pinfunction "BTN-BASE2_P$51") (pintype "output"))
    )
    (net (code "66") (name "SERVO-THREAD") (class "Default")
      (node (ref "AND2.0") (pin "P$4") (pinfunction "PIN_THREAD_P$4") (pintype "bidirectional"))
      (node (ref "AND2.1") (pin "P$4") (pinfunction "PIN_THREAD_P$4") (pintype "bidirectional"))
      (node (ref "AND2.10") (pin "P$4") (pinfunction "PIN_THREAD_P$4") (pintype "bidirectional"))
      (node (ref "AND2.11") (pin "P$4") (pinfunction "PIN_THREAD_P$4") (pintype "bidirectional"))
      (node (ref "AND2.12") (pin "P$4") (pinfunction "PIN_THREAD_P$4") (pintype "bidirectional"))
      (node (ref "AND2.13") (pin "P$4") (pinfunction "PIN_THREAD_P$4") (pintype "bidirectional"))
      (node (ref "AND2.14") (pin "P$4") (pinfunction "PIN_THREAD_P$4") (pintype "bidirectional"))
      (node (ref "AND2.15") (pin "P$4") (pinfunction "PIN_THREAD_P$4") (pintype "bidirectional"))
      (node (ref "AND2.16") (pin "P$4") (pinfunction "PIN_THREAD_P$4") (pintype "bidirectional"))
      (node (ref "AND2.2") (pin "P$4") (pinfunction "PIN_THREAD_P$4") (pintype "bidirectional"))
      (node (ref "AND2.3") (pin "P$4") (pinfunction "PIN_THREAD_P$4") (pintype "bidirectional"))
      (node (ref "AND2.4") (pin "P$4") (pinfunction "PIN_THREAD_P$4") (pintype "bidirectional"))
      (node (ref "AND2.5") (pin "P$4") (pinfunction "PIN_THREAD_P$4") (pintype "bidirectional"))
      (node (ref "AND2.6") (pin "P$4") (pinfunction "PIN_THREAD_P$4") (pintype "bidirectional"))
      (node (ref "AND2.7") (pin "P$4") (pinfunction "PIN_THREAD_P$4") (pintype "bidirectional"))
      (node (ref "AND2.8") (pin "P$4") (pinfunction "PIN_THREAD_P$4") (pintype "bidirectional"))
      (node (ref "AND2.9") (pin "P$4") (pinfunction "PIN_THREAD_P$4") (pintype "bidirectional"))
      (node (ref "CONSTANT.0") (pin "P$1") (pinfunction "PIN_THREAD_P$1") (pintype "bidirectional"))
      (node (ref "CONSTANT.1") (pin "P$1") (pinfunction "PIN_THREAD_P$1") (pintype "bidirectional"))
      (node (ref "CONSTANT.10") (pin "P$1") (pinfunction "PIN_THREAD_P$1") (pintype "bidirectional"))
      (node (ref "CONSTANT.11") (pin "P$1") (pinfunction "PIN_THREAD_P$1") (pintype "bidirectional"))
      (node (ref "CONSTANT.12") (pin "P$1") (pinfunction "PIN_THREAD_P$1") (pintype "bidirectional"))
      (node (ref "CONSTANT.2") (pin "P$1") (pinfunction "PIN_THREAD_P$1") (pintype "bidirectional"))
      (node (ref "CONSTANT.3") (pin "P$1") (pinfunction "PIN_THREAD_P$1") (pintype "bidirectional"))
      (node (ref "CONSTANT.4") (pin "P$1") (pinfunction "PIN_THREAD_P$1") (pintype "bidirectional"))
      (node (ref "CONSTANT.5") (pin "P$1") (pinfunction "PIN_THREAD_P$1") (pintype "bidirectional"))
      (node (ref "CONSTANT.6") (pin "P$1") (pinfunction "PIN_THREAD_P$1") (pintype "bidirectional"))
      (node (ref "CONSTANT.7") (pin "P$1") (pinfunction "PIN_THREAD_P$1") (pintype "bidirectional"))
      (node (ref "CONSTANT.8") (pin "P$1") (pinfunction "PIN_THREAD_P$1") (pintype "bidirectional"))
      (node (ref "CONSTANT.9") (pin "P$1") (pinfunction "PIN_THREAD_P$1") (pintype "bidirectional"))
      (node (ref "CONV-FLOAT-S32.0") (pin "P$1") (pinfunction "PIN_THREAD_P$1") (pintype "bidirectional"))
      (node (ref "FLIPFLOP.0") (pin "P$6") (pinfunction "PIN_THREAD_P$6") (pintype "bidirectional"))
      (node (ref "FLIPFLOP.1") (pin "P$6") (pinfunction "PIN_THREAD_P$6") (pintype "bidirectional"))
      (node (ref "FLIPFLOP.2") (pin "P$6") (pinfunction "PIN_THREAD_P$6") (pintype "bidirectional"))
      (node (ref "FLIPFLOP.3") (pin "P$6") (pinfunction "PIN_THREAD_P$6") (pintype "bidirectional"))
      (node (ref "MUX2.0") (pin "P$1") (pinfunction "PIN_THREAD_P$1") (pintype "bidirectional"))
      (node (ref "MUX2.1") (pin "P$1") (pinfunction "PIN_THREAD_P$1") (pintype "bidirectional"))
      (node (ref "MUX2.2") (pin "P$1") (pinfunction "PIN_THREAD_P$1") (pintype "bidirectional"))
      (node (ref "MUX2.3") (pin "P$1") (pinfunction "PIN_THREAD_P$1") (pintype "bidirectional"))
      (node (ref "MUX2.4") (pin "P$1") (pinfunction "PIN_THREAD_P$1") (pintype "bidirectional"))
      (node (ref "MUX4.0") (pin "P$1") (pinfunction "PIN_THREAD_P$1") (pintype "bidirectional"))
      (node (ref "NOT.0") (pin "P$3") (pinfunction "PIN_THREAD_P$3") (pintype "bidirectional"))
      (node (ref "NOT.1") (pin "P$3") (pinfunction "PIN_THREAD_P$3") (pintype "bidirectional"))
      (node (ref "NOT.2") (pin "P$3") (pinfunction "PIN_THREAD_P$3") (pintype "bidirectional"))
      (node (ref "NOT.3") (pin "P$3") (pinfunction "PIN_THREAD_P$3") (pintype "bidirectional"))
      (node (ref "NOT.4") (pin "P$3") (pinfunction "PIN_THREAD_P$3") (pintype "bidirectional"))
      (node (ref "NOT.5") (pin "P$3") (pinfunction "PIN_THREAD_P$3") (pintype "bidirectional"))
      (node (ref "NOT.6") (pin "P$3") (pinfunction "PIN_THREAD_P$3") (pintype "bidirectional"))
      (node (ref "NOT.7") (pin "P$3") (pinfunction "PIN_THREAD_P$3") (pintype "bidirectional"))
      (node (ref "OR2.0") (pin "P$1") (pinfunction "PIN_THREAD_P$1") (pintype "bidirectional"))
      (node (ref "OR2.1") (pin "P$1") (pinfunction "PIN_THREAD_P$1") (pintype "bidirectional"))
      (node (ref "OR2.10") (pin "P$1") (pinfunction "PIN_THREAD_P$1") (pintype "bidirectional"))
      (node (ref "OR2.11") (pin "P$1") (pinfunction "PIN_THREAD_P$1") (pintype "bidirectional"))
      (node (ref "OR2.12") (pin "P$1") (pinfunction "PIN_THREAD_P$1") (pintype "bidirectional"))
      (node (ref "OR2.13") (pin "P$1") (pinfunction "PIN_THREAD_P$1") (pintype "bidirectional"))
      (node (ref "OR2.2") (pin "P$1") (pinfunction "PIN_THREAD_P$1") (pintype "bidirectional"))
      (node (ref "OR2.3") (pin "P$1") (pinfunction "PIN_THREAD_P$1") (pintype "bidirectional"))
      (node (ref "OR2.4") (pin "P$1") (pinfunction "PIN_THREAD_P$1") (pintype "bidirectional"))
      (node (ref "OR2.5") (pin "P$1") (pinfunction "PIN_THREAD_P$1") (pintype "bidirectional"))
      (node (ref "OR2.6") (pin "P$1") (pinfunction "PIN_THREAD_P$1") (pintype "bidirectional"))
      (node (ref "OR2.7") (pin "P$1") (pinfunction "PIN_THREAD_P$1") (pintype "bidirectional"))
      (node (ref "OR2.8") (pin "P$1") (pinfunction "PIN_THREAD_P$1") (pintype "bidirectional"))
      (node (ref "OR2.9") (pin "P$1") (pinfunction "PIN_THREAD_P$1") (pintype "bidirectional"))
      (node (ref "SCALE.0") (pin "P$1") (pinfunction "PIN_THREAD_P$1") (pintype "bidirectional"))
      (node (ref "SCALE.1") (pin "P$1") (pinfunction "PIN_THREAD_P$1") (pintype "bidirectional"))
      (node (ref "SCALE.2") (pin "P$1") (pinfunction "PIN_THREAD_P$1") (pintype "bidirectional"))
      (node (ref "SCALE.3") (pin "P$1") (pinfunction "PIN_THREAD_P$1") (pintype "bidirectional"))
      (node (ref "SCALE.4") (pin "P$1") (pinfunction "PIN_THREAD_P$1") (pintype "bidirectional"))
      (node (ref "SCALE.5") (pin "P$1") (pinfunction "PIN_THREAD_P$1") (pintype "bidirectional"))
      (node (ref "SCALE.6") (pin "P$1") (pinfunction "PIN_THREAD_P$1") (pintype "bidirectional"))
      (node (ref "SERVO-THREAD") (pin "P$7") (pinfunction "__P$7") (pintype "output"))
      (node (ref "TIMEDELAY.0") (pin "P$6") (pinfunction "PIN_THREAD_P$6") (pintype "bidirectional"))
      (node (ref "TOGGLE.0") (pin "P$1") (pinfunction "PIN_THREAD_P$1") (pintype "bidirectional"))
    )
    (net (code "67") (name "VEL-PER-MINUTE") (class "Default")
      (node (ref "SCALE.0") (pin "P$5") (pinfunction "OUT_P$5") (pintype "output"))
      (node (ref "SCALE.1") (pin "P$3") (pinfunction "IN_P$3") (pintype "input"))
      (node (ref "SCALE.2") (pin "P$3") (pinfunction "IN_P$3") (pintype "input"))
    )
    (net (code "68") (name "VEL-PER-SECOND") (class "Default")
      (node (ref "MUX2.0") (pin "P$4") (pinfunction "OUT_P$4") (pintype "output"))
      (node (ref "SCALE.0") (pin "P$3") (pinfunction "IN_P$3") (pintype "input"))
    )
    (net (code "69") (name "X-ANALOG") (class "Default")
      (node (ref "HALUI.JOG.0") (pin "P$1") (pinfunction "ANALOG_P$1") (pintype "input"))
      (node (ref "MUX2.1") (pin "P$4") (pinfunction "OUT_P$4") (pintype "output"))
    )
    (net (code "70") (name "X-DISABLE") (class "Default")
      (node (ref "AND2.4") (pin "P$2") (pinfunction "IN1_P$2") (pintype "input"))
      (node (ref "NOT.4") (pin "P$2") (pinfunction "OUT_P$2") (pintype "output"))
    )
    (net (code "71") (name "X-ENABLE") (class "Default")
      (node (ref "FLIPFLOP.0") (pin "P$3") (pinfunction "OUT_P$3") (pintype "output"))
      (node (ref "MUX2.1") (pin "P$5") (pinfunction "SEL_P$5") (pintype "input"))
      (node (ref "NOT.4") (pin "P$1") (pinfunction "IN_P$1") (pintype "input"))
    )
    (net (code "72") (name "X-HAT-MINUS") (class "Default")
      (node (ref "AND2.9") (pin "P$1") (pinfunction "IN0_P$1") (pintype "input"))
      (node (ref "INPUT.0") (pin "P$4") (pinfunction "ABS-HAT0X-IS-NEG_P$4") (pintype "output"))
      (node (ref "OR2.4") (pin "P$3") (pinfunction "IN1_P$3") (pintype "input"))
    )
    (net (code "73") (name "X-HAT-PLUS") (class "Default")
      (node (ref "AND2.10") (pin "P$1") (pinfunction "IN0_P$1") (pintype "input"))
      (node (ref "INPUT.0") (pin "P$5") (pinfunction "ABS-HAT0X-IS-POS_P$5") (pintype "output"))
      (node (ref "OR2.4") (pin "P$2") (pinfunction "IN0_P$2") (pintype "input"))
    )
    (net (code "74") (name "X-JOG") (class "Default")
      (node (ref "INPUT.0") (pin "P$31") (pinfunction "ABS-X-POSITION_P$31") (pintype "output"))
      (node (ref "MUX2.1") (pin "P$3") (pinfunction "IN1_P$3") (pintype "input"))
    )
    (net (code "75") (name "X-KNOB-ACTIVE") (class "Default")
      (node (ref "AND2.1") (pin "P$1") (pinfunction "IN0_P$1") (pintype "input"))
      (node (ref "NOT.0") (pin "P$1") (pinfunction "IN_P$1") (pintype "input"))
      (node (ref "OR2.7") (pin "P$4") (pinfunction "OUT_P$4") (pintype "output"))
    )
    (net (code "76") (name "X-KNOB-INACTIVE") (class "Default")
      (node (ref "AND2.2") (pin "P$1") (pinfunction "IN0_P$1") (pintype "input"))
      (node (ref "AND2.3") (pin "P$1") (pinfunction "IN0_P$1") (pintype "input"))
      (node (ref "NOT.0") (pin "P$2") (pinfunction "OUT_P$2") (pintype "output"))
    )
    (net (code "77") (name "X-SET") (class "Default")
      (node (ref "AND2.1") (pin "P$3") (pinfunction "OUT_P$3") (pintype "output"))
      (node (ref "FLIPFLOP.0") (pin "P$5") (pinfunction "SET_P$5") (pintype "input"))
    )
    (net (code "78") (name "XY-BUTTONS-ACTIVE") (class "Default")
      (node (ref "OR2.12") (pin "P$2") (pinfunction "IN0_P$2") (pintype "input"))
      (node (ref "OR2.13") (pin "P$3") (pinfunction "IN1_P$3") (pintype "input"))
      (node (ref "OR2.5") (pin "P$4") (pinfunction "OUT_P$4") (pintype "output"))
    )
    (net (code "79") (name "XY-RESET") (class "Default")
      (node (ref "AND2.2") (pin "P$3") (pinfunction "OUT_P$3") (pintype "output"))
      (node (ref "FLIPFLOP.0") (pin "P$4") (pinfunction "RESET_P$4") (pintype "input"))
      (node (ref "FLIPFLOP.1") (pin "P$4") (pinfunction "RESET_P$4") (pintype "input"))
    )
    (net (code "80") (name "XYZA-BUTTONS-ACTIVE") (class "Default")
      (node (ref "OR2.13") (pin "P$4") (pinfunction "OUT_P$4") (pintype "output"))
      (node (ref "TIMEDELAY.0") (pin "P$2") (pinfunction "IN_P$2") (pintype "input"))
    )
    (net (code "81") (name "Y-ANALOG") (class "Default")
      (node (ref "HALUI.JOG.1") (pin "P$1") (pinfunction "ANALOG_P$1") (pintype "input"))
      (node (ref "MUX2.2") (pin "P$4") (pinfunction "OUT_P$4") (pintype "output"))
    )
    (net (code "82") (name "Y-DISABLE") (class "Default")
      (node (ref "AND2.1") (pin "P$2") (pinfunction "IN1_P$2") (pintype "input"))
      (node (ref "NOT.5") (pin "P$2") (pinfunction "OUT_P$2") (pintype "output"))
    )
    (net (code "83") (name "Y-ENABLE") (class "Default")
      (node (ref "FLIPFLOP.1") (pin "P$3") (pinfunction "OUT_P$3") (pintype "output"))
      (node (ref "MUX2.2") (pin "P$5") (pinfunction "SEL_P$5") (pintype "input"))
      (node (ref "NOT.5") (pin "P$1") (pinfunction "IN_P$1") (pintype "input"))
    )
    (net (code "84") (name "Y-HAT-MINUS") (class "Default")
      (node (ref "AND2.12") (pin "P$1") (pinfunction "IN0_P$1") (pintype "input"))
      (node (ref "INPUT.0") (pin "P$16") (pinfunction "ABS-HAT0Y-IS-NEG_P$16") (pintype "output"))
      (node (ref "OR2.6") (pin "P$3") (pinfunction "IN1_P$3") (pintype "input"))
    )
    (net (code "85") (name "Y-HAT-PLUS") (class "Default")
      (node (ref "AND2.11") (pin "P$1") (pinfunction "IN0_P$1") (pintype "input"))
      (node (ref "INPUT.0") (pin "P$12") (pinfunction "ABS-HAT0Y-IS-POS_P$12") (pintype "output"))
      (node (ref "OR2.6") (pin "P$2") (pinfunction "IN0_P$2") (pintype "input"))
    )
    (net (code "86") (name "Y-JOG") (class "Default")
      (node (ref "INPUT.0") (pin "P$39") (pinfunction "ABS-Y-POSITION_P$39") (pintype "output"))
      (node (ref "SCALE.5") (pin "P$3") (pinfunction "IN_P$3") (pintype "input"))
    )
    (net (code "87") (name "Y-KNOB-ACTIVE") (class "Default")
      (node (ref "AND2.3") (pin "P$2") (pinfunction "IN1_P$2") (pintype "input"))
      (node (ref "NOT.1") (pin "P$1") (pinfunction "IN_P$1") (pintype "input"))
      (node (ref "OR2.8") (pin "P$4") (pinfunction "OUT_P$4") (pintype "output"))
    )
    (net (code "88") (name "Y-KNOB-INACTIVE") (class "Default")
      (node (ref "AND2.2") (pin "P$2") (pinfunction "IN1_P$2") (pintype "input"))
      (node (ref "NOT.1") (pin "P$2") (pinfunction "OUT_P$2") (pintype "output"))
    )
    (net (code "89") (name "Y-SELECT") (class "Default")
      (node (ref "AND2.3") (pin "P$3") (pinfunction "OUT_P$3") (pintype "output"))
      (node (ref "AND2.4") (pin "P$1") (pinfunction "IN0_P$1") (pintype "input"))
    )
    (net (code "90") (name "Y-SET") (class "Default")
      (node (ref "AND2.4") (pin "P$3") (pinfunction "OUT_P$3") (pintype "output"))
      (node (ref "FLIPFLOP.1") (pin "P$5") (pinfunction "SET_P$5") (pintype "input"))
    )
    (net (code "91") (name "Z-ANALOG") (class "Default")
      (node (ref "HALUI.JOG.2") (pin "P$1") (pinfunction "ANALOG_P$1") (pintype "input"))
      (node (ref "MUX2.3") (pin "P$4") (pinfunction "OUT_P$4") (pintype "output"))
    )
    (net (code "92") (name "Z-BUTTON-MINUS") (class "Default")
      (node (ref "AND2.13") (pin "P$1") (pinfunction "IN0_P$1") (pintype "input"))
      (node (ref "INPUT.0") (pin "P$65") (pinfunction "BTN-THUMB_P$65") (pintype "output"))
      (node (ref "OR2.2") (pin "P$2") (pinfunction "IN0_P$2") (pintype "input"))
    )
    (net (code "93") (name "Z-BUTTON-PLUS") (class "Default")
      (node (ref "AND2.14") (pin "P$1") (pinfunction "IN0_P$1") (pintype "input"))
      (node (ref "INPUT.0") (pin "P$69") (pinfunction "BTN-TOP_P$69") (pintype "output"))
      (node (ref "OR2.2") (pin "P$3") (pinfunction "IN1_P$3") (pintype "input"))
    )
    (net (code "94") (name "Z-BUTTONS-ACTIVE") (class "Default")
      (node (ref "OR2.1") (pin "P$3") (pinfunction "IN1_P$3") (pintype "input"))
      (node (ref "OR2.2") (pin "P$4") (pinfunction "OUT_P$4") (pintype "output"))
    )
    (net (code "95") (name "Z-DISABLE") (class "Default")
      (node (ref "AND2.8") (pin "P$2") (pinfunction "IN1_P$2") (pintype "input"))
      (node (ref "NOT.6") (pin "P$2") (pinfunction "OUT_P$2") (pintype "output"))
    )
    (net (code "96") (name "Z-ENABLE") (class "Default")
      (node (ref "FLIPFLOP.2") (pin "P$3") (pinfunction "OUT_P$3") (pintype "output"))
      (node (ref "MUX2.3") (pin "P$5") (pinfunction "SEL_P$5") (pintype "input"))
      (node (ref "NOT.6") (pin "P$1") (pinfunction "IN_P$1") (pintype "input"))
    )
    (net (code "97") (name "Z-JOG") (class "Default")
      (node (ref "INPUT.0") (pin "P$23") (pinfunction "ABS-RZ-POSITION_P$23") (pintype "output"))
      (node (ref "SCALE.6") (pin "P$3") (pinfunction "IN_P$3") (pintype "input"))
    )
    (net (code "98") (name "Z-KNOB-ACTIVE") (class "Default")
      (node (ref "AND2.5") (pin "P$1") (pinfunction "IN0_P$1") (pintype "input"))
      (node (ref "NOT.3") (pin "P$1") (pinfunction "IN_P$1") (pintype "input"))
      (node (ref "OR2.10") (pin "P$4") (pinfunction "OUT_P$4") (pintype "output"))
    )
    (net (code "99") (name "Z-KNOB-INACTIVE") (class "Default")
      (node (ref "AND2.6") (pin "P$1") (pinfunction "IN0_P$1") (pintype "input"))
      (node (ref "AND2.7") (pin "P$1") (pinfunction "IN0_P$1") (pintype "input"))
      (node (ref "NOT.3") (pin "P$2") (pinfunction "OUT_P$2") (pintype "output"))
    )
    (net (code "100") (name "Z-SET") (class "Default")
      (node (ref "AND2.5") (pin "P$3") (pinfunction "OUT_P$3") (pintype "output"))
      (node (ref "FLIPFLOP.2") (pin "P$5") (pinfunction "SET_P$5") (pintype "input"))
    )
    (net (code "101") (name "unconnected-(CONV-FLOAT-S32.0C-OUT-OF-RANGE-PadP$5)") (class "Default")
      (node (ref "CONV-FLOAT-S32.0") (pin "P$5") (pinfunction "OUT-OF-RANGE_P$5") (pintype "output"))
    )
    (net (code "102") (name "unconnected-(FLIPFLOP.0B-CLK-PadP$1)") (class "Default")
      (node (ref "FLIPFLOP.0") (pin "P$1") (pinfunction "CLK_P$1") (pintype "input"))
    )
    (net (code "103") (name "unconnected-(FLIPFLOP.0B-DATA-PadP$2)") (class "Default")
      (node (ref "FLIPFLOP.0") (pin "P$2") (pinfunction "DATA_P$2") (pintype "input"))
    )
    (net (code "104") (name "unconnected-(FLIPFLOP.1B-CLK-PadP$1)") (class "Default")
      (node (ref "FLIPFLOP.1") (pin "P$1") (pinfunction "CLK_P$1") (pintype "input"))
    )
    (net (code "105") (name "unconnected-(FLIPFLOP.1B-DATA-PadP$2)") (class "Default")
      (node (ref "FLIPFLOP.1") (pin "P$2") (pinfunction "DATA_P$2") (pintype "input"))
    )
    (net (code "106") (name "unconnected-(FLIPFLOP.2B-CLK-PadP$1)") (class "Default")
      (node (ref "FLIPFLOP.2") (pin "P$1") (pinfunction "CLK_P$1") (pintype "input"))
    )
    (net (code "107") (name "unconnected-(FLIPFLOP.2B-DATA-PadP$2)") (class "Default")
      (node (ref "FLIPFLOP.2") (pin "P$2") (pinfunction "DATA_P$2") (pintype "input"))
    )
    (net (code "108") (name "unconnected-(FLIPFLOP.3B-CLK-PadP$1)") (class "Default")
      (node (ref "FLIPFLOP.3") (pin "P$1") (pinfunction "CLK_P$1") (pintype "input"))
    )
    (net (code "109") (name "unconnected-(FLIPFLOP.3B-DATA-PadP$2)") (class "Default")
      (node (ref "FLIPFLOP.3") (pin "P$2") (pinfunction "DATA_P$2") (pintype "input"))
    )
    (net (code "110") (name "unconnected-(HALUID-MODE.AUTO-PadP$65)") (class "Default")
      (node (ref "HALUI") (pin "P$65") (pinfunction "MODE.AUTO_P$65") (pintype "input"))
    )
    (net (code "111") (name "unconnected-(HALUID-MODE.IS-AUTO-PadP$66)") (class "Default")
      (node (ref "HALUI") (pin "P$66") (pinfunction "MODE.IS-AUTO_P$66") (pintype "output"))
    )
    (net (code "112") (name "unconnected-(HALUID-MODE.IS-JOINT-PadP$67)") (class "Default")
      (node (ref "HALUI") (pin "P$67") (pinfunction "MODE.IS-JOINT_P$67") (pintype "output"))
    )
    (net (code "113") (name "unconnected-(HALUID-MODE.IS-MANUAL-PadP$68)") (class "Default")
      (node (ref "HALUI") (pin "P$68") (pinfunction "MODE.IS-MANUAL_P$68") (pintype "output"))
    )
    (net (code "114") (name "unconnected-(HALUID-MODE.IS-MDI-PadP$69)") (class "Default")
      (node (ref "HALUI") (pin "P$69") (pinfunction "MODE.IS-MDI_P$69") (pintype "output"))
    )
    (net (code "115") (name "unconnected-(HALUID-MODE.IS-TELEOP-PadP$70)") (class "Default")
      (node (ref "HALUI") (pin "P$70") (pinfunction "MODE.IS-TELEOP_P$70") (pintype "output"))
    )
    (net (code "116") (name "unconnected-(HALUID-MODE.JOINT-PadP$71)") (class "Default")
      (node (ref "HALUI") (pin "P$71") (pinfunction "MODE.JOINT_P$71") (pintype "input"))
    )
    (net (code "117") (name "unconnected-(HALUID-MODE.MDI-PadP$73)") (class "Default")
      (node (ref "HALUI") (pin "P$73") (pinfunction "MODE.MDI_P$73") (pintype "input"))
    )
    (net (code "118") (name "unconnected-(HALUID-MODE.TELEOP-PadP$74)") (class "Default")
      (node (ref "HALUI") (pin "P$74") (pinfunction "MODE.TELEOP_P$74") (pintype "input"))
    )
    (net (code "119") (name "unconnected-(HALUIE-PROGRAM.BLOCK-DELETE.IS-ON-PadP$33)") (class "Default")
      (node (ref "HALUI") (pin "P$33") (pinfunction "PROGRAM.BLOCK-DELETE.IS-ON_P$33") (pintype "output"))
    )
    (net (code "120") (name "unconnected-(HALUIE-PROGRAM.BLOCK-DELETE.OFF-PadP$34)") (class "Default")
      (node (ref "HALUI") (pin "P$34") (pinfunction "PROGRAM.BLOCK-DELETE.OFF_P$34") (pintype "input"))
    )
    (net (code "121") (name "unconnected-(HALUIE-PROGRAM.BLOCK-DELETE.ON-PadP$35)") (class "Default")
      (node (ref "HALUI") (pin "P$35") (pinfunction "PROGRAM.BLOCK-DELETE.ON_P$35") (pintype "input"))
    )
    (net (code "122") (name "unconnected-(HALUIE-PROGRAM.IS-IDLE-PadP$36)") (class "Default")
      (node (ref "HALUI") (pin "P$36") (pinfunction "PROGRAM.IS-IDLE_P$36") (pintype "output"))
    )
    (net (code "123") (name "unconnected-(HALUIE-PROGRAM.IS-PAUSED-PadP$37)") (class "Default")
      (node (ref "HALUI") (pin "P$37") (pinfunction "PROGRAM.IS-PAUSED_P$37") (pintype "output"))
    )
    (net (code "124") (name "unconnected-(HALUIE-PROGRAM.IS-RUNNING-PadP$38)") (class "Default")
      (node (ref "HALUI") (pin "P$38") (pinfunction "PROGRAM.IS-RUNNING_P$38") (pintype "output"))
    )
    (net (code "125") (name "unconnected-(HALUIE-PROGRAM.OPTIONAL-STOP.IS-ON-PadP$39)") (class "Default")
      (node (ref "HALUI") (pin "P$39") (pinfunction "PROGRAM.OPTIONAL-STOP.IS-ON_P$39") (pintype "output"))
    )
    (net (code "126") (name "unconnected-(HALUIE-PROGRAM.OPTIONAL-STOP.OFF-PadP$40)") (class "Default")
      (node (ref "HALUI") (pin "P$40") (pinfunction "PROGRAM.OPTIONAL-STOP.OFF_P$40") (pintype "input"))
    )
    (net (code "127") (name "unconnected-(HALUIE-PROGRAM.OPTIONAL-STOP.ON-PadP$41)") (class "Default")
      (node (ref "HALUI") (pin "P$41") (pinfunction "PROGRAM.OPTIONAL-STOP.ON_P$41") (pintype "input"))
    )
    (net (code "128") (name "unconnected-(HALUIE-PROGRAM.PAUSE-PadP$42)") (class "Default")
      (node (ref "HALUI") (pin "P$42") (pinfunction "PROGRAM.PAUSE_P$42") (pintype "input"))
    )
    (net (code "129") (name "unconnected-(HALUIE-PROGRAM.RUN-PadP$44)") (class "Default")
      (node (ref "HALUI") (pin "P$44") (pinfunction "PROGRAM.RUN_P$44") (pintype "input"))
    )
    (net (code "130") (name "unconnected-(HALUIE-PROGRAM.STEP-PadP$45)") (class "Default")
      (node (ref "HALUI") (pin "P$45") (pinfunction "PROGRAM.STEP_P$45") (pintype "input"))
    )
    (net (code "131") (name "unconnected-(HALUIE-PROGRAM.STOP-PadP$46)") (class "Default")
      (node (ref "HALUI") (pin "P$46") (pinfunction "PROGRAM.STOP_P$46") (pintype "input"))
    )
    (net (code "132") (name "unconnected-(HALUIH-ABORT-PadP$1)") (class "Default")
      (node (ref "HALUI") (pin "P$1") (pinfunction "ABORT_P$1") (pintype "input"))
    )
    (net (code "133") (name "unconnected-(HALUIH-ESTOP.IS-ACTIVATED-PadP$3)") (class "Default")
      (node (ref "HALUI") (pin "P$3") (pinfunction "ESTOP.IS-ACTIVATED_P$3") (pintype "output"))
    )
    (net (code "134") (name "unconnected-(HALUIH-MACHINE.IS-ON-PadP$5)") (class "Default")
      (node (ref "HALUI") (pin "P$5") (pinfunction "MACHINE.IS-ON_P$5") (pintype "output"))
    )
    (net (code "135") (name "unconnected-(HALUIH-MACHINE.OFF-PadP$6)") (class "Default")
      (node (ref "HALUI") (pin "P$6") (pinfunction "MACHINE.OFF_P$6") (pintype "input"))
    )
    (net (code "136") (name "unconnected-(HALUIH-MACHINE.ON-PadP$7)") (class "Default")
      (node (ref "HALUI") (pin "P$7") (pinfunction "MACHINE.ON_P$7") (pintype "input"))
    )
    (net (code "137") (name "unconnected-(INPUT.0A-ABS-HAT0X-COUNTS-PadP$1)") (class "Default")
      (node (ref "INPUT.0") (pin "P$1") (pinfunction "ABS-HAT0X-COUNTS_P$1") (pintype "output"))
    )
    (net (code "138") (name "unconnected-(INPUT.0A-ABS-HAT0X-FLAT-PadP$2)") (class "Default")
      (node (ref "INPUT.0") (pin "P$2") (pinfunction "ABS-HAT0X-FLAT_P$2") (pintype "input"))
    )
    (net (code "139") (name "unconnected-(INPUT.0A-ABS-HAT0X-FUZZ-PadP$3)") (class "Default")
      (node (ref "INPUT.0") (pin "P$3") (pinfunction "ABS-HAT0X-FUZZ_P$3") (pintype "input"))
    )
    (net (code "140") (name "unconnected-(INPUT.0A-ABS-HAT0X-OFFSET-PadP$6)") (class "Default")
      (node (ref "INPUT.0") (pin "P$6") (pinfunction "ABS-HAT0X-OFFSET_P$6") (pintype "input"))
    )
    (net (code "141") (name "unconnected-(INPUT.0A-ABS-HAT0X-POSITION-PadP$7)") (class "Default")
      (node (ref "INPUT.0") (pin "P$7") (pinfunction "ABS-HAT0X-POSITION_P$7") (pintype "output"))
    )
    (net (code "142") (name "unconnected-(INPUT.0A-ABS-HAT0X-SCALE-PadP$8)") (class "Default")
      (node (ref "INPUT.0") (pin "P$8") (pinfunction "ABS-HAT0X-SCALE_P$8") (pintype "input"))
    )
    (net (code "143") (name "unconnected-(INPUT.0A-ABS-HAT0Y-COUNTS-PadP$9)") (class "Default")
      (node (ref "INPUT.0") (pin "P$9") (pinfunction "ABS-HAT0Y-COUNTS_P$9") (pintype "output"))
    )
    (net (code "144") (name "unconnected-(INPUT.0A-ABS-HAT0Y-FLAT-PadP$10)") (class "Default")
      (node (ref "INPUT.0") (pin "P$10") (pinfunction "ABS-HAT0Y-FLAT_P$10") (pintype "input"))
    )
    (net (code "145") (name "unconnected-(INPUT.0A-ABS-HAT0Y-FUZZ-PadP$11)") (class "Default")
      (node (ref "INPUT.0") (pin "P$11") (pinfunction "ABS-HAT0Y-FUZZ_P$11") (pintype "input"))
    )
    (net (code "146") (name "unconnected-(INPUT.0A-ABS-HAT0Y-OFFSET-PadP$13)") (class "Default")
      (node (ref "INPUT.0") (pin "P$13") (pinfunction "ABS-HAT0Y-OFFSET_P$13") (pintype "input"))
    )
    (net (code "147") (name "unconnected-(INPUT.0A-ABS-HAT0Y-POSITION-PadP$14)") (class "Default")
      (node (ref "INPUT.0") (pin "P$14") (pinfunction "ABS-HAT0Y-POSITION_P$14") (pintype "output"))
    )
    (net (code "148") (name "unconnected-(INPUT.0A-ABS-HAT0Y-SCALE-PadP$15)") (class "Default")
      (node (ref "INPUT.0") (pin "P$15") (pinfunction "ABS-HAT0Y-SCALE_P$15") (pintype "input"))
    )
    (net (code "149") (name "unconnected-(INPUT.0A-ABS-RZ-COUNTS-PadP$17)") (class "Default")
      (node (ref "INPUT.0") (pin "P$17") (pinfunction "ABS-RZ-COUNTS_P$17") (pintype "output"))
    )
    (net (code "150") (name "unconnected-(INPUT.0A-ABS-RZ-FUZZ-PadP$19)") (class "Default")
      (node (ref "INPUT.0") (pin "P$19") (pinfunction "ABS-RZ-FUZZ_P$19") (pintype "input"))
    )
    (net (code "151") (name "unconnected-(INPUT.0A-ABS-RZ-OFFSET-PadP$22)") (class "Default")
      (node (ref "INPUT.0") (pin "P$22") (pinfunction "ABS-RZ-OFFSET_P$22") (pintype "input"))
    )
    (net (code "152") (name "unconnected-(INPUT.0A-ABS-RZ-SCALE-PadP$24)") (class "Default")
      (node (ref "INPUT.0") (pin "P$24") (pinfunction "ABS-RZ-SCALE_P$24") (pintype "input"))
    )
    (net (code "153") (name "unconnected-(INPUT.0A-ABS-X-COUNTS-PadP$25)") (class "Default")
      (node (ref "INPUT.0") (pin "P$25") (pinfunction "ABS-X-COUNTS_P$25") (pintype "output"))
    )
    (net (code "154") (name "unconnected-(INPUT.0A-ABS-X-FUZZ-PadP$27)") (class "Default")
      (node (ref "INPUT.0") (pin "P$27") (pinfunction "ABS-X-FUZZ_P$27") (pintype "input"))
    )
    (net (code "155") (name "unconnected-(INPUT.0A-ABS-X-OFFSET-PadP$30)") (class "Default")
      (node (ref "INPUT.0") (pin "P$30") (pinfunction "ABS-X-OFFSET_P$30") (pintype "input"))
    )
    (net (code "156") (name "unconnected-(INPUT.0A-ABS-X-SCALE-PadP$32)") (class "Default")
      (node (ref "INPUT.0") (pin "P$32") (pinfunction "ABS-X-SCALE_P$32") (pintype "input"))
    )
    (net (code "157") (name "unconnected-(INPUT.0A-ABS-Y-COUNTS-PadP$33)") (class "Default")
      (node (ref "INPUT.0") (pin "P$33") (pinfunction "ABS-Y-COUNTS_P$33") (pintype "output"))
    )
    (net (code "158") (name "unconnected-(INPUT.0A-ABS-Y-FUZZ-PadP$35)") (class "Default")
      (node (ref "INPUT.0") (pin "P$35") (pinfunction "ABS-Y-FUZZ_P$35") (pintype "input"))
    )
    (net (code "159") (name "unconnected-(INPUT.0A-ABS-Y-OFFSET-PadP$38)") (class "Default")
      (node (ref "INPUT.0") (pin "P$38") (pinfunction "ABS-Y-OFFSET_P$38") (pintype "input"))
    )
    (net (code "160") (name "unconnected-(INPUT.0A-ABS-Y-SCALE-PadP$40)") (class "Default")
      (node (ref "INPUT.0") (pin "P$40") (pinfunction "ABS-Y-SCALE_P$40") (pintype "input"))
    )
    (net (code "161") (name "unconnected-(INPUT.0A-ABS-Z-COUNTS-PadP$41)") (class "Default")
      (node (ref "INPUT.0") (pin "P$41") (pinfunction "ABS-Z-COUNTS_P$41") (pintype "output"))
    )
    (net (code "162") (name "unconnected-(INPUT.0A-ABS-Z-FUZZ-PadP$43)") (class "Default")
      (node (ref "INPUT.0") (pin "P$43") (pinfunction "ABS-Z-FUZZ_P$43") (pintype "input"))
    )
    (net (code "163") (name "unconnected-(INPUT.0A-ABS-Z-OFFSET-PadP$46)") (class "Default")
      (node (ref "INPUT.0") (pin "P$46") (pinfunction "ABS-Z-OFFSET_P$46") (pintype "input"))
    )
    (net (code "164") (name "unconnected-(INPUT.0A-ABS-Z-SCALE-PadP$48)") (class "Default")
      (node (ref "INPUT.0") (pin "P$48") (pinfunction "ABS-Z-SCALE_P$48") (pintype "input"))
    )
    (net (code "165") (name "unconnected-(INPUT.0B-BTN-BASE-NOT-PadP$50)") (class "Default")
      (node (ref "INPUT.0") (pin "P$50") (pinfunction "BTN-BASE-NOT_P$50") (pintype "output"))
    )
    (net (code "166") (name "unconnected-(INPUT.0B-BTN-BASE2-NOT-PadP$52)") (class "Default")
      (node (ref "INPUT.0") (pin "P$52") (pinfunction "BTN-BASE2-NOT_P$52") (pintype "output"))
    )
    (net (code "167") (name "unconnected-(INPUT.0B-BTN-BASE3-NOT-PadP$54)") (class "Default")
      (node (ref "INPUT.0") (pin "P$54") (pinfunction "BTN-BASE3-NOT_P$54") (pintype "output"))
    )
    (net (code "168") (name "unconnected-(INPUT.0B-BTN-BASE4-NOT-PadP$56)") (class "Default")
      (node (ref "INPUT.0") (pin "P$56") (pinfunction "BTN-BASE4-NOT_P$56") (pintype "output"))
    )
    (net (code "169") (name "unconnected-(INPUT.0B-BTN-BASE5-NOT-PadP$58)") (class "Default")
      (node (ref "INPUT.0") (pin "P$58") (pinfunction "BTN-BASE5-NOT_P$58") (pintype "output"))
    )
    (net (code "170") (name "unconnected-(INPUT.0B-BTN-BASE6-NOT-PadP$60)") (class "Default")
      (node (ref "INPUT.0") (pin "P$60") (pinfunction "BTN-BASE6-NOT_P$60") (pintype "output"))
    )
    (net (code "171") (name "unconnected-(INPUT.0B-BTN-JOYSTICK-NOT-PadP$62)") (class "Default")
      (node (ref "INPUT.0") (pin "P$62") (pinfunction "BTN-JOYSTICK-NOT_P$62") (pintype "output"))
    )
    (net (code "172") (name "unconnected-(INPUT.0B-BTN-PINKIE-NOT-PadP$64)") (class "Default")
      (node (ref "INPUT.0") (pin "P$64") (pinfunction "BTN-PINKIE-NOT_P$64") (pintype "output"))
    )
    (net (code "173") (name "unconnected-(INPUT.0B-BTN-PINKIE-PadP$63)") (class "Default")
      (node (ref "INPUT.0") (pin "P$63") (pinfunction "BTN-PINKIE_P$63") (pintype "output"))
    )
    (net (code "174") (name "unconnected-(INPUT.0B-BTN-THUMB-NOT-PadP$66)") (class "Default")
      (node (ref "INPUT.0") (pin "P$66") (pinfunction "BTN-THUMB-NOT_P$66") (pintype "output"))
    )
    (net (code "175") (name "unconnected-(INPUT.0B-BTN-THUMB2-NOT-PadP$68)") (class "Default")
      (node (ref "INPUT.0") (pin "P$68") (pinfunction "BTN-THUMB2-NOT_P$68") (pintype "output"))
    )
    (net (code "176") (name "unconnected-(INPUT.0B-BTN-TOP-NOT-PadP$70)") (class "Default")
      (node (ref "INPUT.0") (pin "P$70") (pinfunction "BTN-TOP-NOT_P$70") (pintype "output"))
    )
    (net (code "177") (name "unconnected-(INPUT.0B-BTN-TOP2-NOT-PadP$72)") (class "Default")
      (node (ref "INPUT.0") (pin "P$72") (pinfunction "BTN-TOP2-NOT_P$72") (pintype "output"))
    )
    (net (code "178") (name "unconnected-(SCALE.0B-OFFSET-PadP$4)") (class "Default")
      (node (ref "SCALE.0") (pin "P$4") (pinfunction "OFFSET_P$4") (pintype "input"))
    )
    (net (code "179") (name "unconnected-(SCALE.1B-OFFSET-PadP$4)") (class "Default")
      (node (ref "SCALE.1") (pin "P$4") (pinfunction "OFFSET_P$4") (pintype "input"))
    )
    (net (code "180") (name "unconnected-(SCALE.2B-OFFSET-PadP$4)") (class "Default")
      (node (ref "SCALE.2") (pin "P$4") (pinfunction "OFFSET_P$4") (pintype "input"))
    )
    (net (code "181") (name "unconnected-(SCALE.3B-OFFSET-PadP$4)") (class "Default")
      (node (ref "SCALE.3") (pin "P$4") (pinfunction "OFFSET_P$4") (pintype "input"))
    )
    (net (code "182") (name "unconnected-(SCALE.4B-OFFSET-PadP$4)") (class "Default")
      (node (ref "SCALE.4") (pin "P$4") (pinfunction "OFFSET_P$4") (pintype "input"))
    )
    (net (code "183") (name "unconnected-(SCALE.5B-OFFSET-PadP$4)") (class "Default")
      (node (ref "SCALE.5") (pin "P$4") (pinfunction "OFFSET_P$4") (pintype "input"))
    )
    (net (code "184") (name "unconnected-(SCALE.6B-OFFSET-PadP$4)") (class "Default")
      (node (ref "SCALE.6") (pin "P$4") (pinfunction "OFFSET_P$4") (pintype "input"))
    )
    (net (code "185") (name "unconnected-(SERVO-THREAD--1-PadP$1)") (class "Default")
      (node (ref "SERVO-THREAD") (pin "P$1") (pinfunction "-1_P$1") (pintype "output"))
    )
    (net (code "186") (name "unconnected-(SERVO-THREAD--2-PadP$2)") (class "Default")
      (node (ref "SERVO-THREAD") (pin "P$2") (pinfunction "-2_P$2") (pintype "output"))
    )
    (net (code "187") (name "unconnected-(SERVO-THREAD--3-PadP$3)") (class "Default")
      (node (ref "SERVO-THREAD") (pin "P$3") (pinfunction "-3_P$3") (pintype "output"))
    )
    (net (code "188") (name "unconnected-(SERVO-THREAD-1-PadP$4)") (class "Default")
      (node (ref "SERVO-THREAD") (pin "P$4") (pinfunction "1_P$4") (pintype "output"))
    )
    (net (code "189") (name "unconnected-(SERVO-THREAD-2-PadP$5)") (class "Default")
      (node (ref "SERVO-THREAD") (pin "P$5") (pinfunction "2_P$5") (pintype "output"))
    )
    (net (code "190") (name "unconnected-(SERVO-THREAD-3-PadP$6)") (class "Default")
      (node (ref "SERVO-THREAD") (pin "P$6") (pinfunction "3_P$6") (pintype "output"))
    )
    (net (code "191") (name "unconnected-(TIMEDELAY.0B-ELAPSED-PadP$1)") (class "Default")
      (node (ref "TIMEDELAY.0") (pin "P$1") (pinfunction "ELAPSED_P$1") (pintype "output"))
    )
  )
)
